# stopwatch.net
KiCad netlist of a schematic drawn in EAGLE
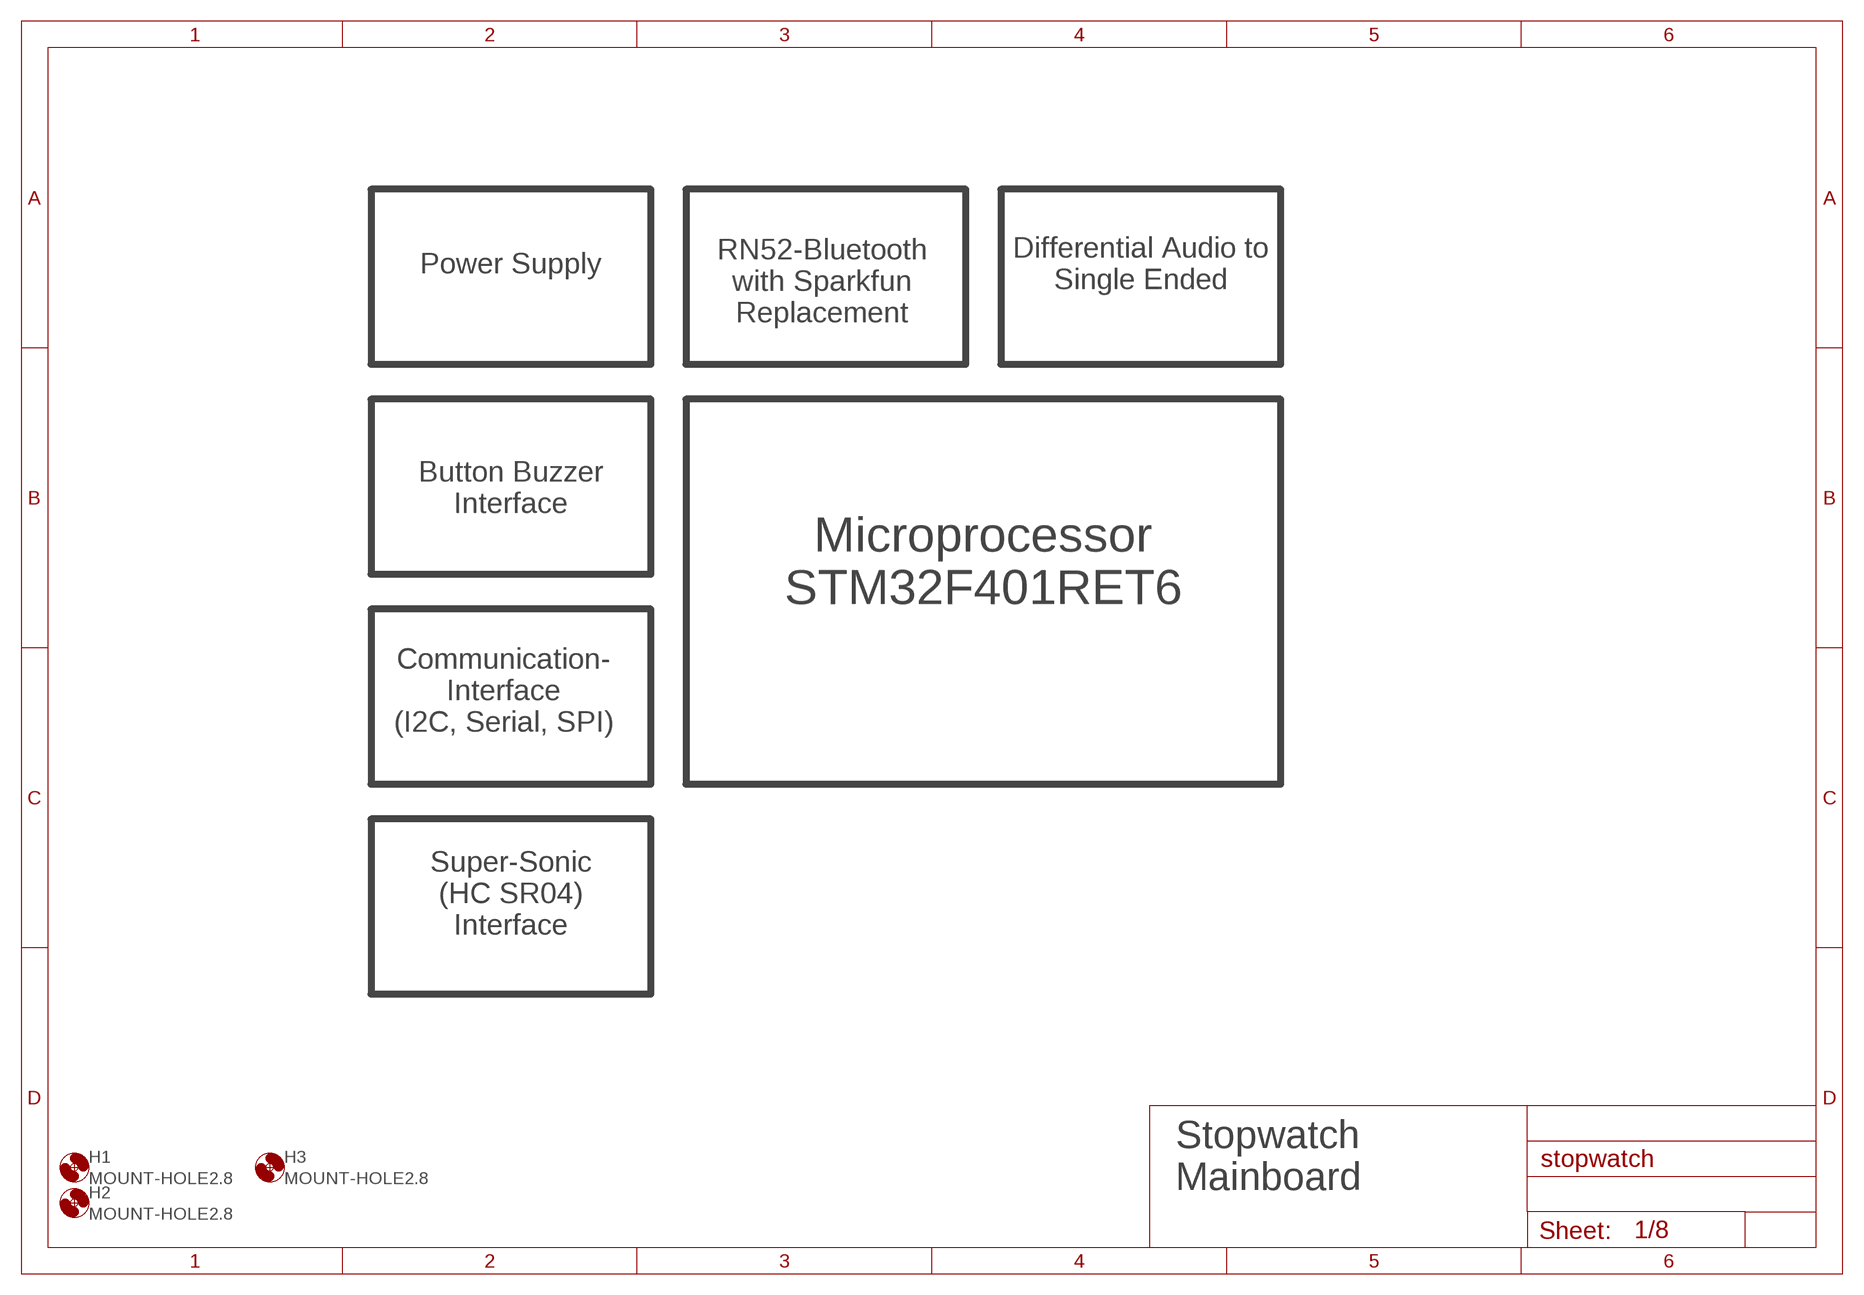
[diagram p0: schematic, sheet 1]
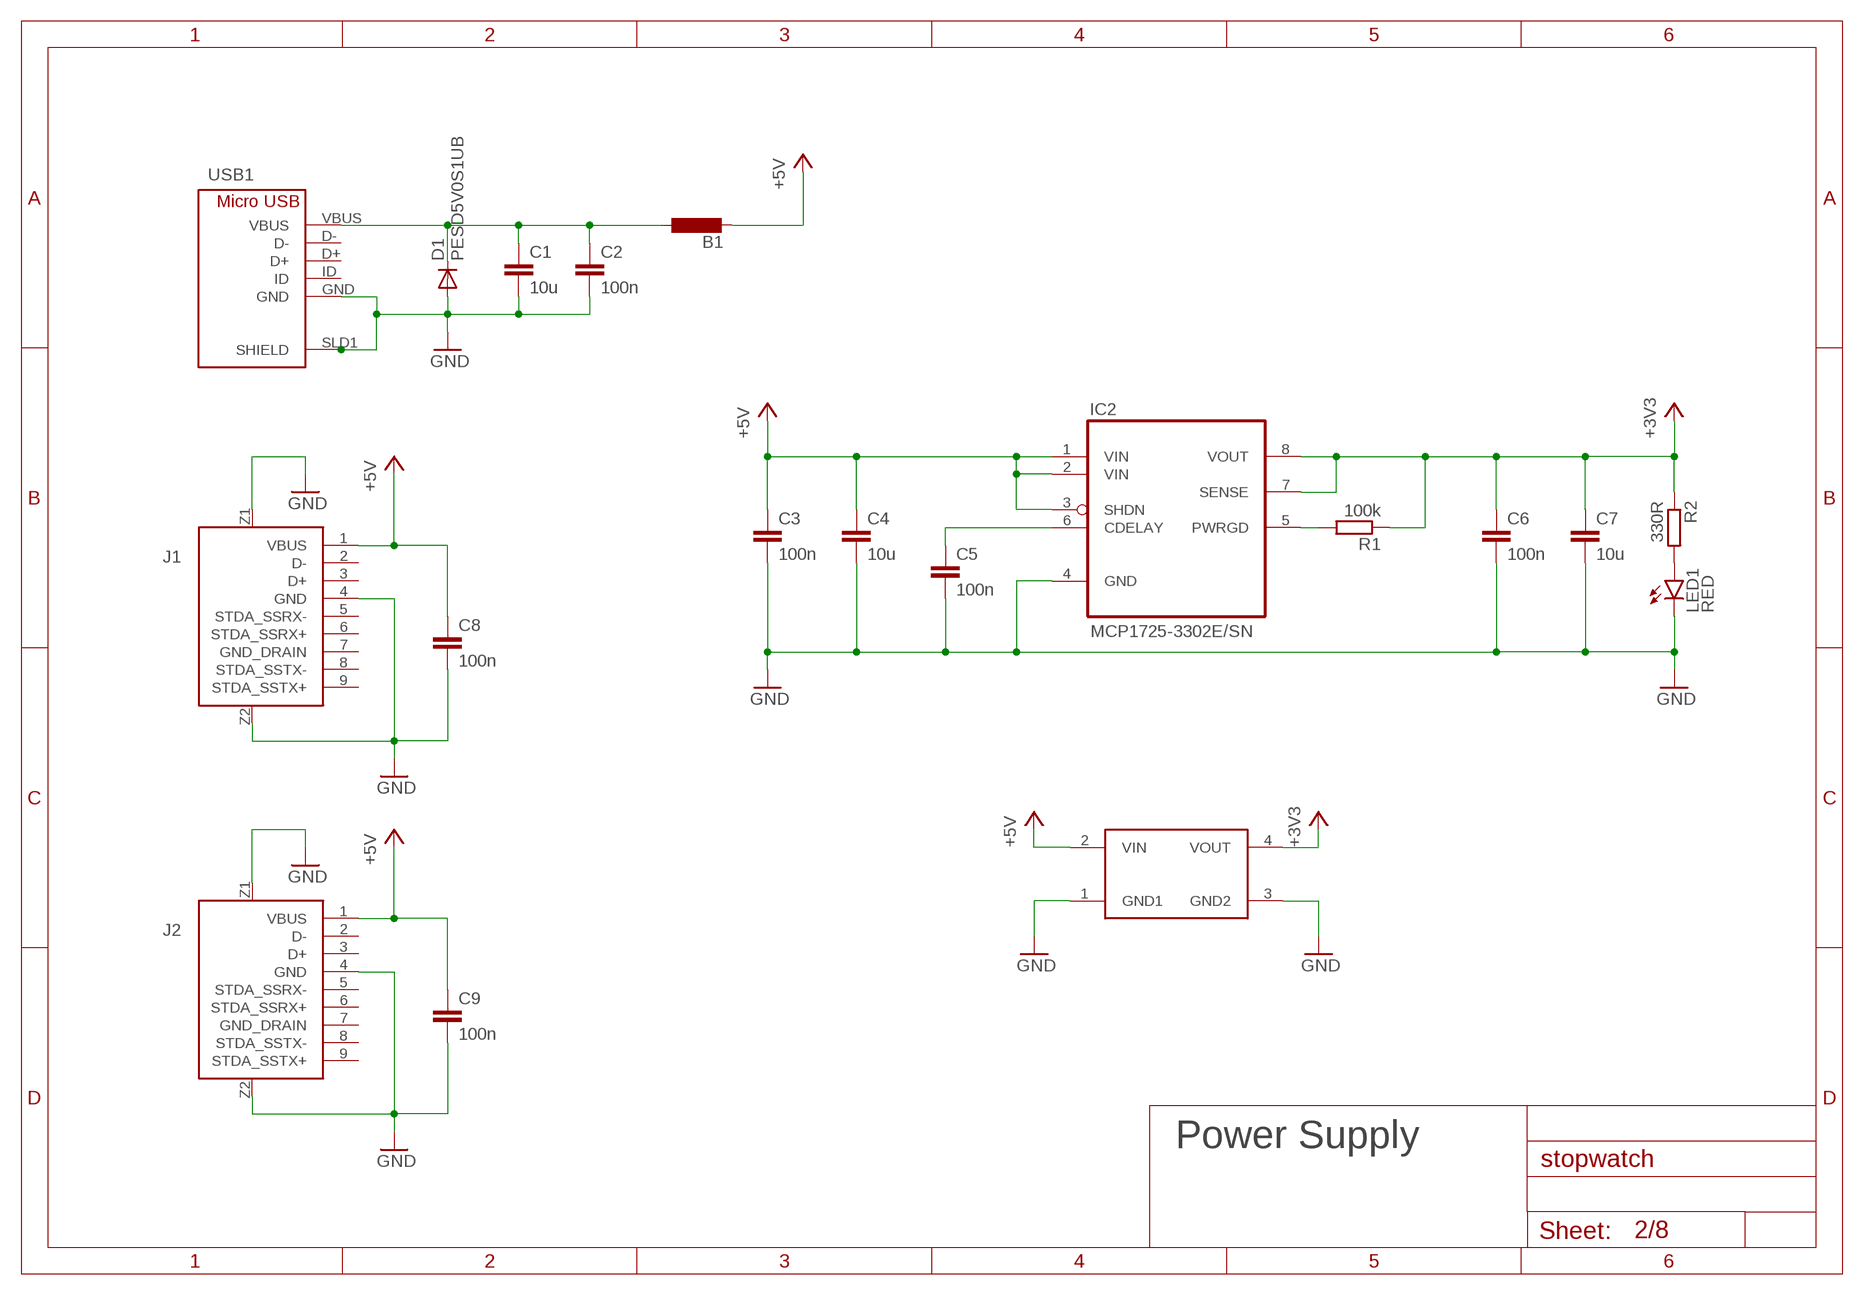
[diagram p1: schematic, sheet 2]
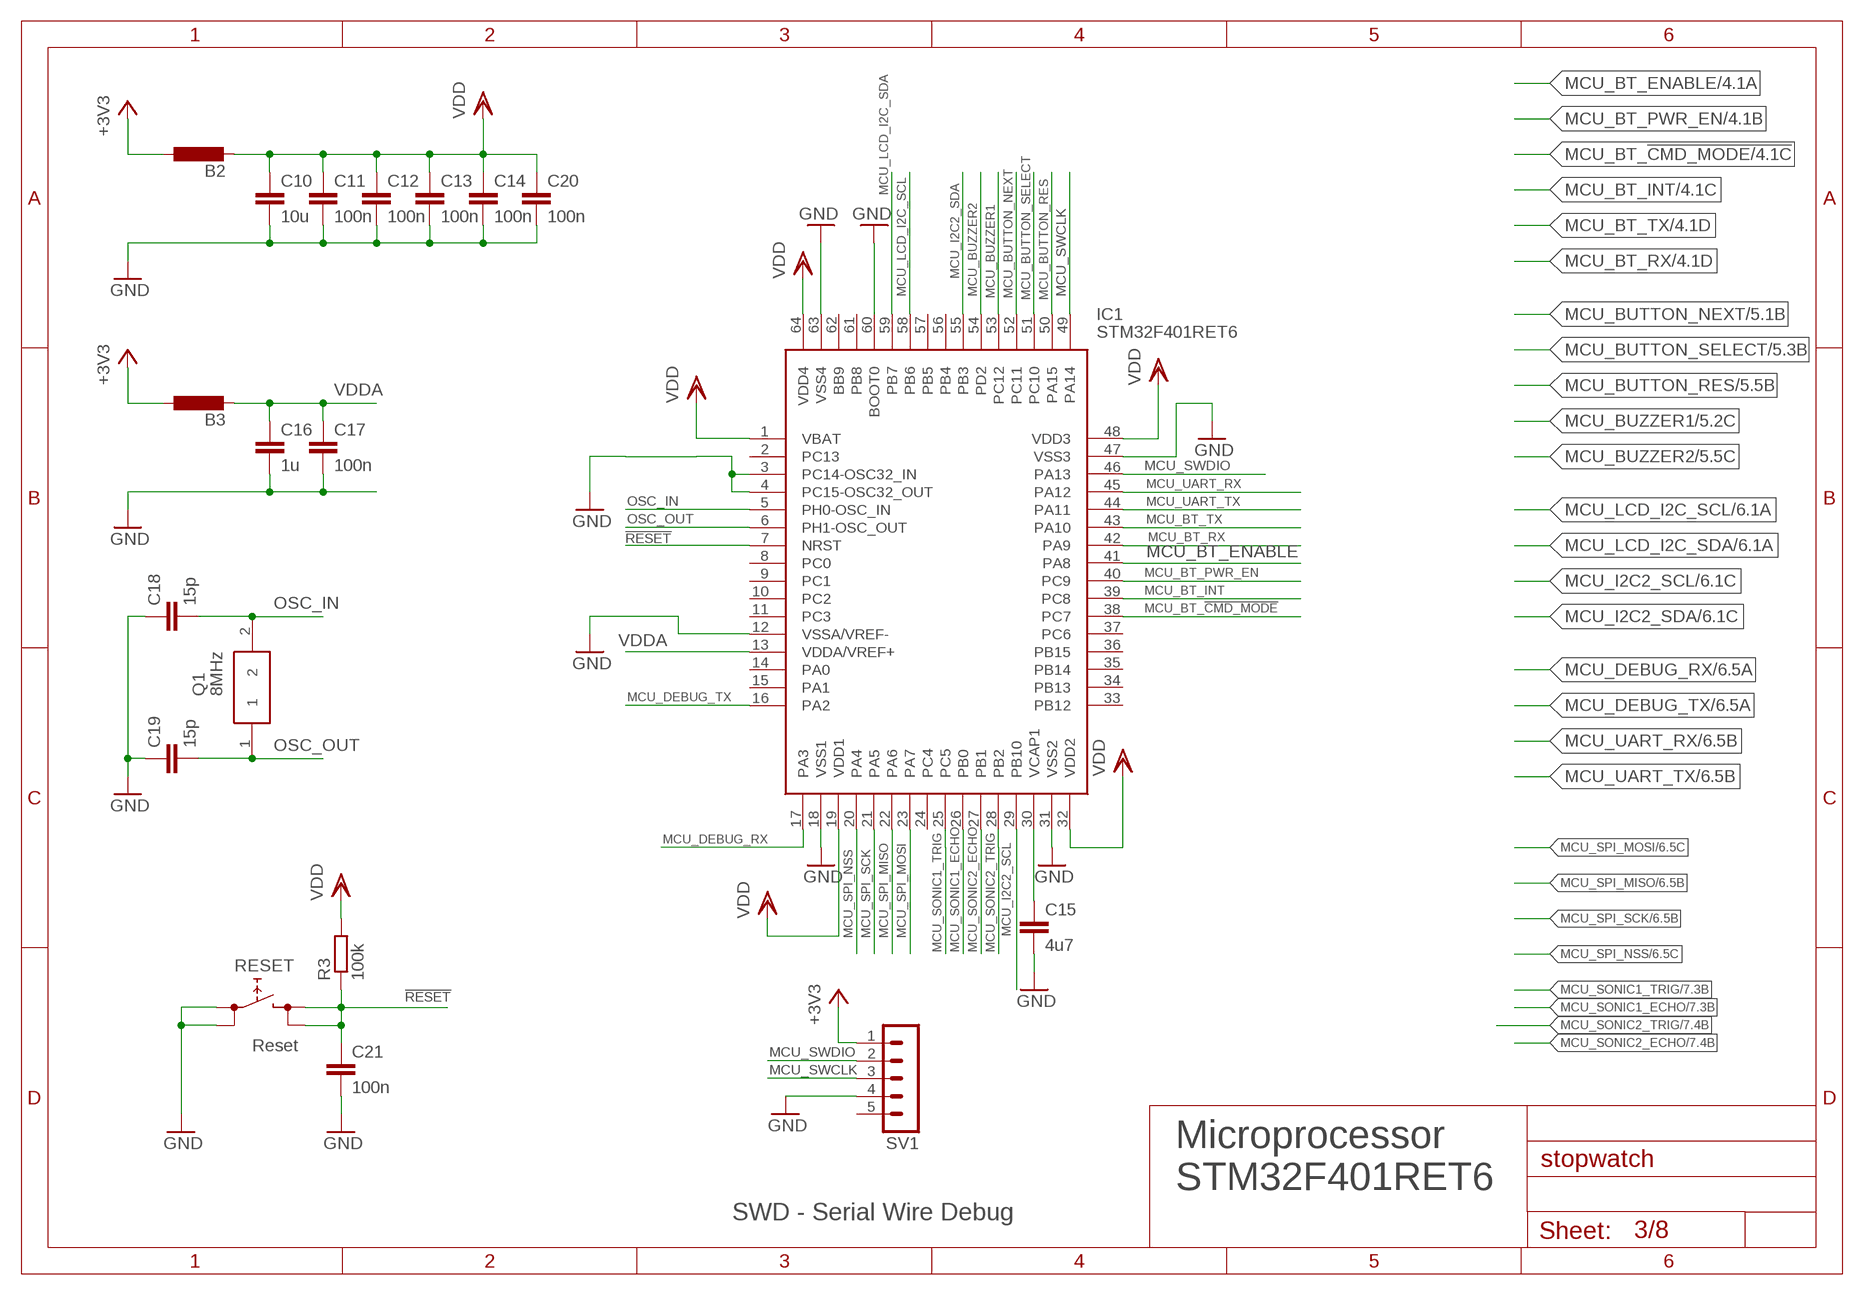
[diagram p2: schematic, sheet 3]
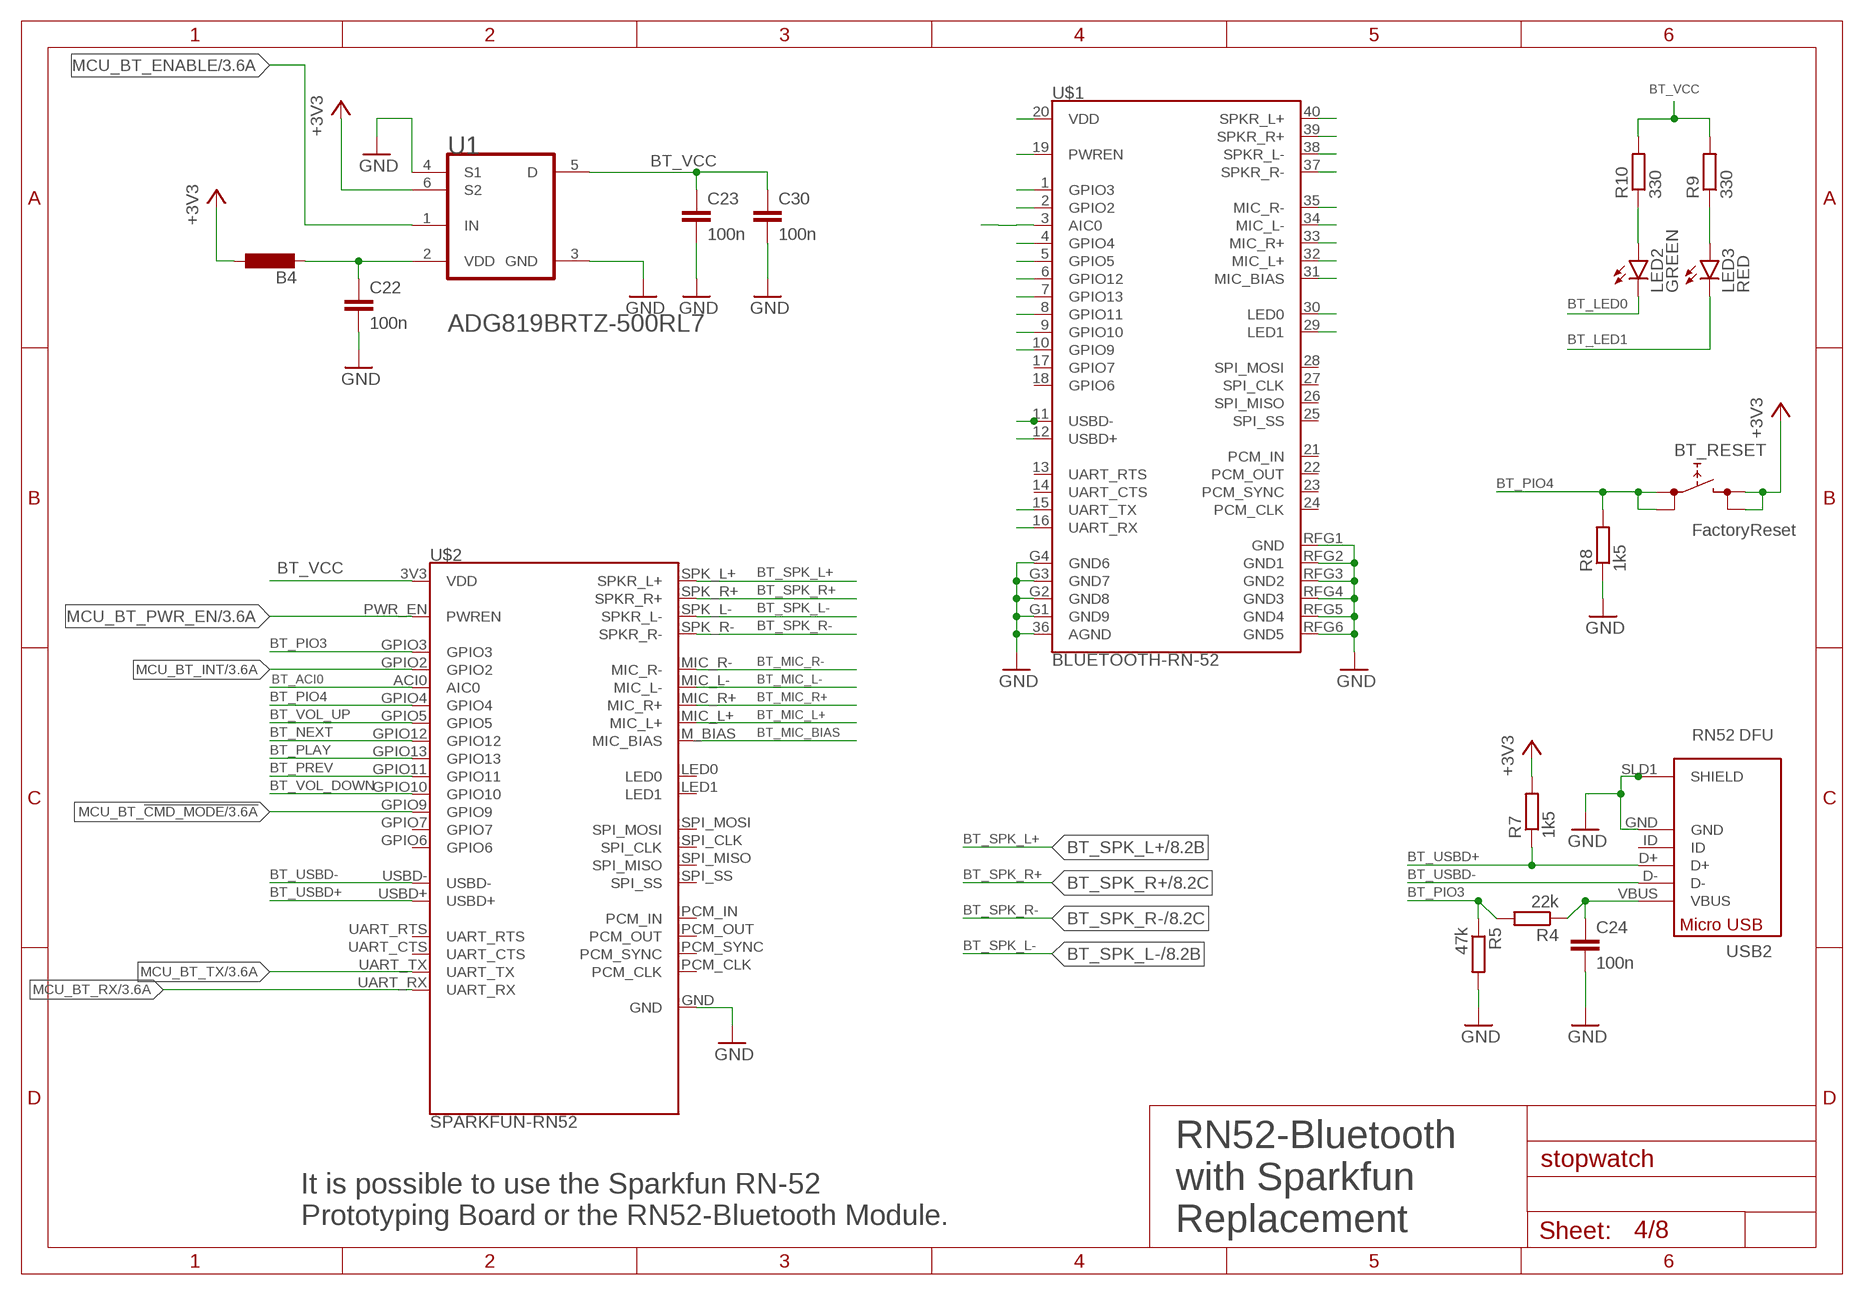
[diagram p3: schematic, sheet 4]
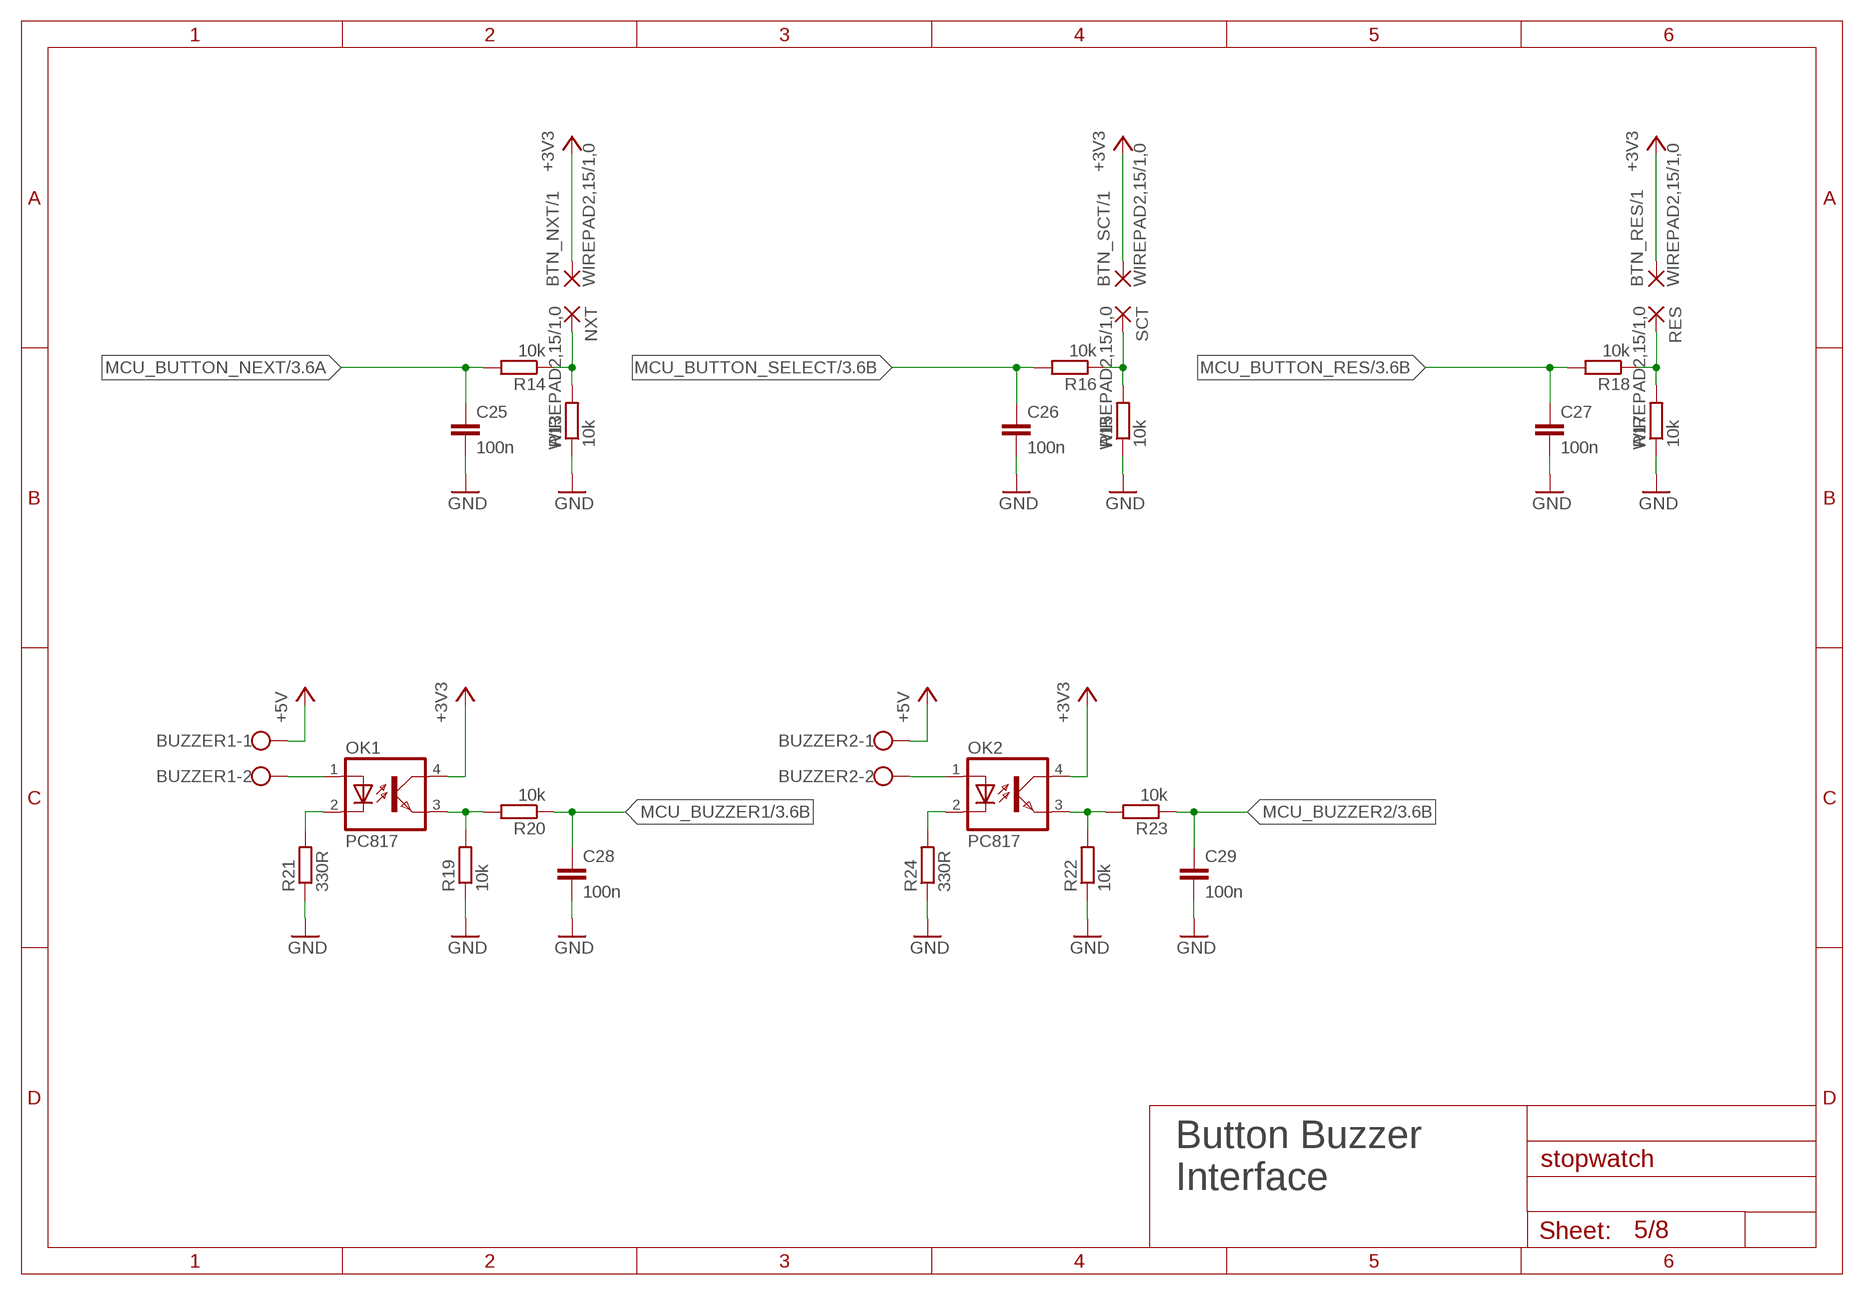
[diagram p4: schematic, sheet 5]
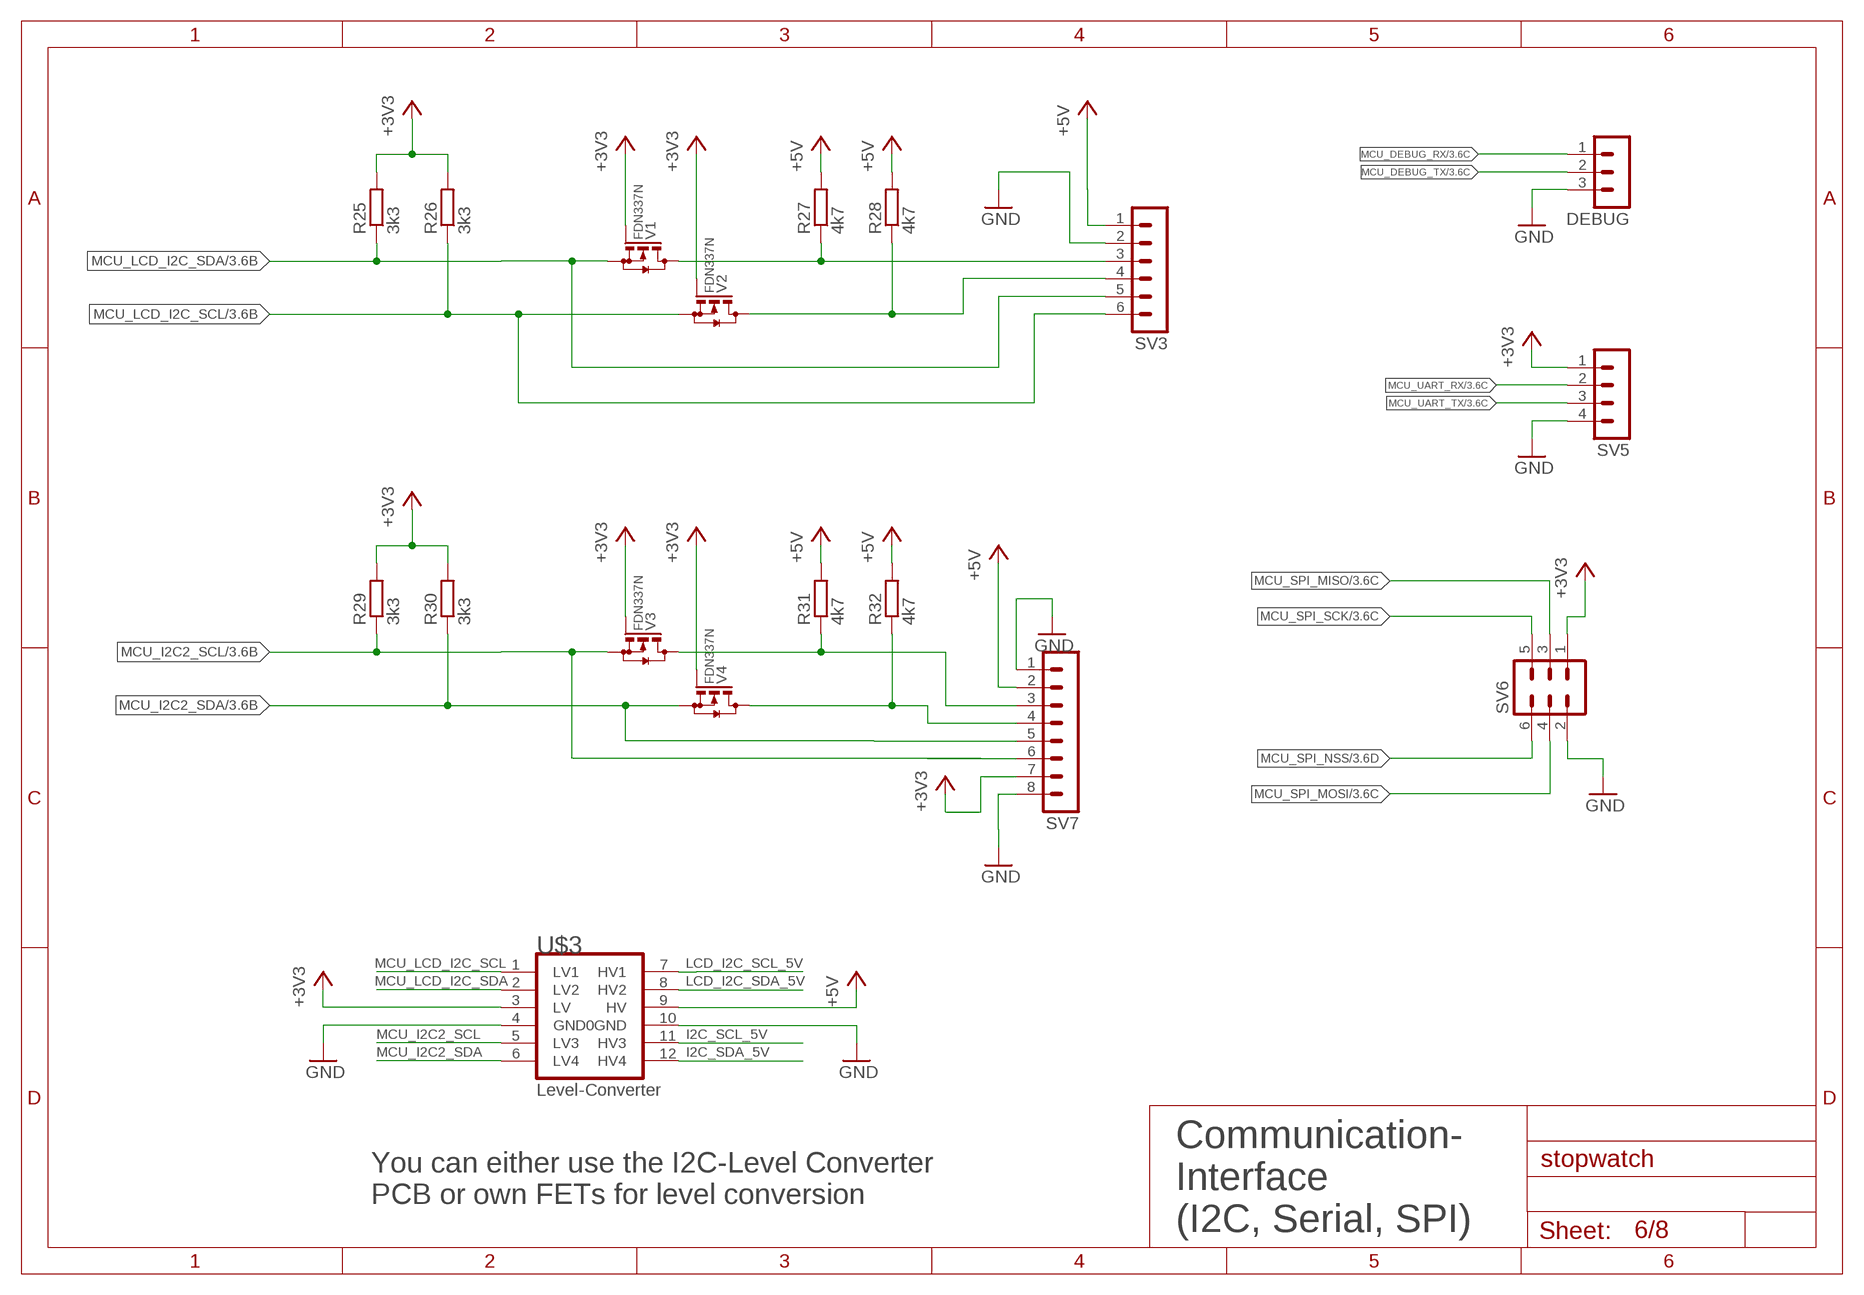
[diagram p5: schematic, sheet 6]
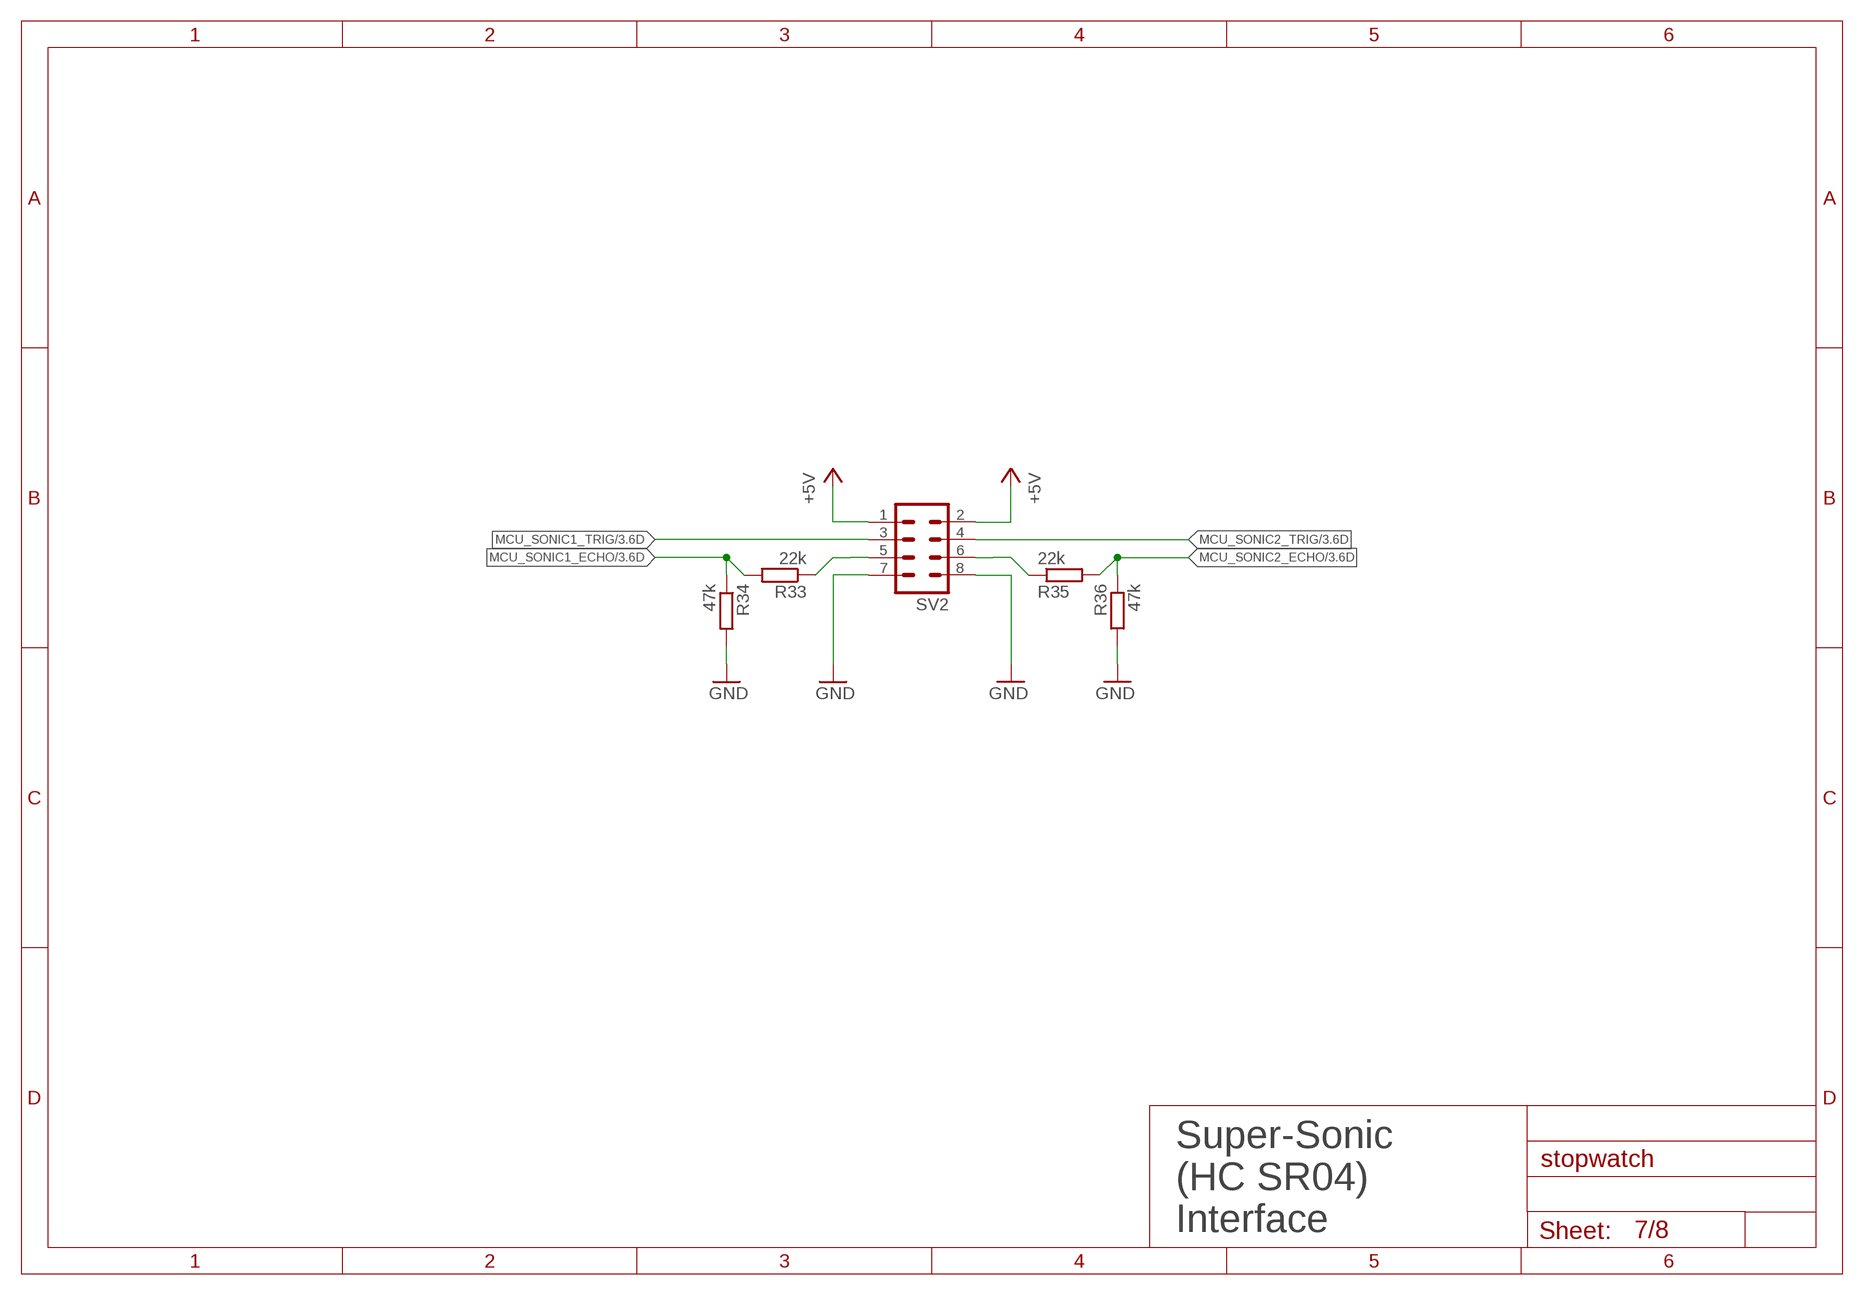
[diagram p6: schematic, sheet 7]
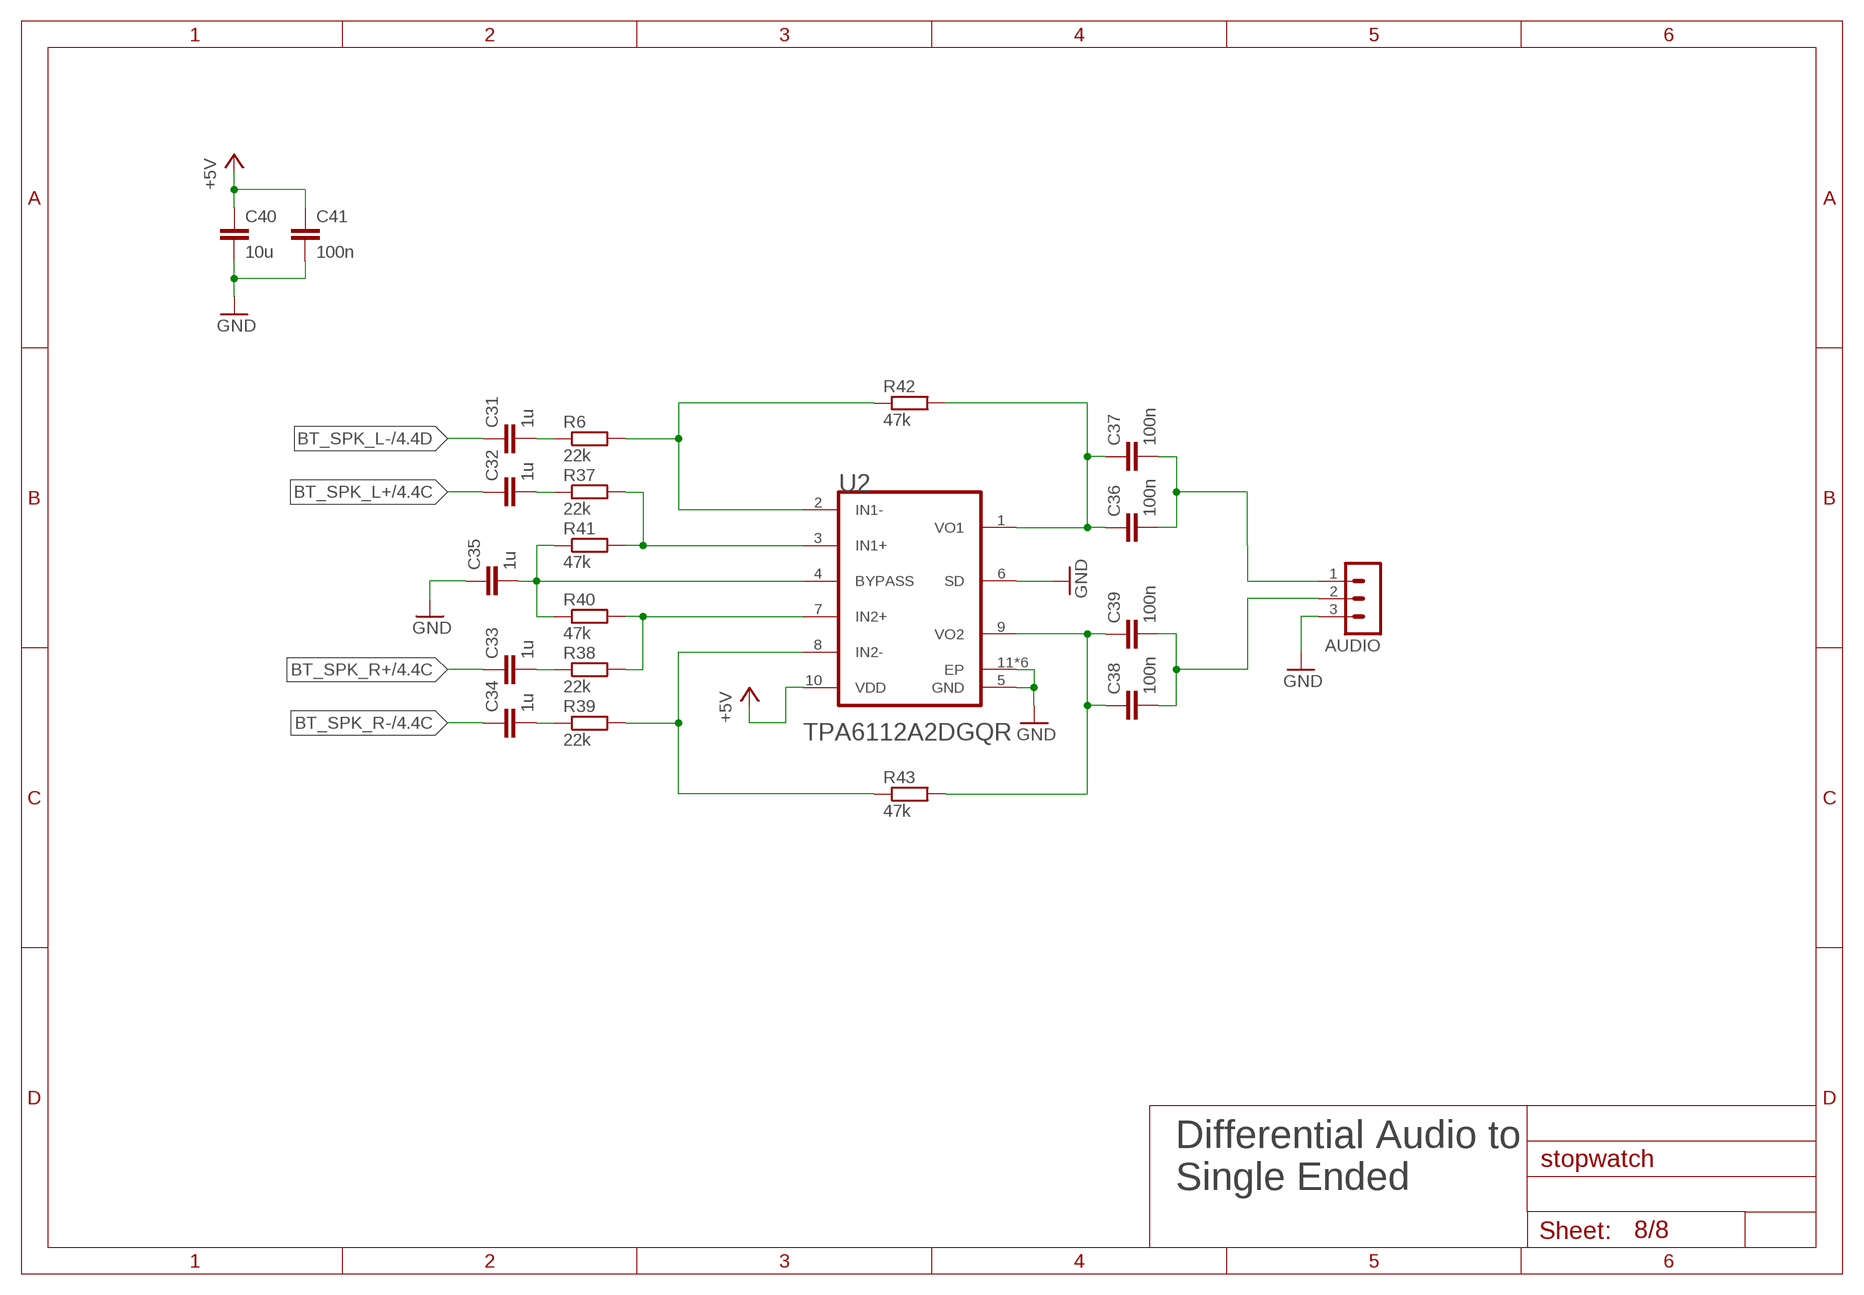
[diagram p7: schematic, sheet 8]

(export (version "E")
  (design (tool "Eeschema 10.0.6"))
  (components
    (comp (ref "BTN_NXT/1")
      (value "WIREPAD2,15/1,0")
      (footprint "eagle-import:2,15_1,0")
      (libsource (lib "eagle-import") (part "WIREPAD2,15/1,0"))
    )
    (comp (ref "BTN_RES/1")
      (value "WIREPAD2,15/1,0")
      (footprint "eagle-import:2,15_1,0")
      (libsource (lib "eagle-import") (part "WIREPAD2,15/1,0"))
    )
    (comp (ref "BTN_SCT/1")
      (value "WIREPAD2,15/1,0")
      (footprint "eagle-import:2,15_1,0")
      (libsource (lib "eagle-import") (part "WIREPAD2,15/1,0"))
    )
    (comp (ref "BUZZER1")
      (value "W237-102")
      (footprint "eagle-import:W237-102")
      (fields (field (name "MPN") "237-102"))
      (libsource (lib "eagle-import") (part "W237-102"))
    )
    (comp (ref "BUZZER2")
      (value "W237-102")
      (footprint "eagle-import:W237-102")
      (fields (field (name "MPN") "237-102"))
      (libsource (lib "eagle-import") (part "W237-102"))
    )
    (comp (ref "C25")
      (value "100n")
      (footprint "eagle-import:C1206")
      (libsource (lib "eagle-import") (part "C-EUC1206"))
    )
    (comp (ref "C26")
      (value "100n")
      (footprint "eagle-import:C1206")
      (libsource (lib "eagle-import") (part "C-EUC1206"))
    )
    (comp (ref "C27")
      (value "100n")
      (footprint "eagle-import:C1206")
      (libsource (lib "eagle-import") (part "C-EUC1206"))
    )
    (comp (ref "C28")
      (value "100n")
      (footprint "eagle-import:C1206")
      (libsource (lib "eagle-import") (part "C-EUC1206"))
    )
    (comp (ref "C29")
      (value "100n")
      (footprint "eagle-import:C1206")
      (libsource (lib "eagle-import") (part "C-EUC1206"))
    )
    (comp (ref "NXT")
      (value "WIREPAD2,15/1,0")
      (footprint "eagle-import:2,15_1,0")
      (libsource (lib "eagle-import") (part "WIREPAD2,15/1,0"))
    )
    (comp (ref "OK1")
      (value "PC817")
      (footprint "eagle-import:DIL04")
      (fields (field (name "MPN") "PC817X4J000F"))
      (libsource (lib "eagle-import") (part "PC817"))
    )
    (comp (ref "OK2")
      (value "PC817")
      (footprint "eagle-import:DIL04")
      (fields (field (name "MPN") "PC817X4J000F"))
      (libsource (lib "eagle-import") (part "PC817"))
    )
    (comp (ref "R13")
      (value "10k")
      (footprint "eagle-import:R1206")
      (libsource (lib "eagle-import") (part "R-EU_R1206"))
    )
    (comp (ref "R14")
      (value "10k")
      (footprint "eagle-import:R1206")
      (libsource (lib "eagle-import") (part "R-EU_R1206"))
    )
    (comp (ref "R15")
      (value "10k")
      (footprint "eagle-import:R1206")
      (libsource (lib "eagle-import") (part "R-EU_R1206"))
    )
    (comp (ref "R16")
      (value "10k")
      (footprint "eagle-import:R1206")
      (libsource (lib "eagle-import") (part "R-EU_R1206"))
    )
    (comp (ref "R17")
      (value "10k")
      (footprint "eagle-import:R1206")
      (libsource (lib "eagle-import") (part "R-EU_R1206"))
    )
    (comp (ref "R18")
      (value "10k")
      (footprint "eagle-import:R1206")
      (libsource (lib "eagle-import") (part "R-EU_R1206"))
    )
    (comp (ref "R19")
      (value "10k")
      (footprint "eagle-import:R1206")
      (libsource (lib "eagle-import") (part "R-EU_R1206"))
    )
    (comp (ref "R20")
      (value "10k")
      (footprint "eagle-import:R1206")
      (libsource (lib "eagle-import") (part "R-EU_R1206"))
    )
    (comp (ref "R21")
      (value "330R")
      (footprint "eagle-import:R1206")
      (libsource (lib "eagle-import") (part "R-EU_R1206"))
    )
    (comp (ref "R22")
      (value "10k")
      (footprint "eagle-import:R1206")
      (libsource (lib "eagle-import") (part "R-EU_R1206"))
    )
    (comp (ref "R23")
      (value "10k")
      (footprint "eagle-import:R1206")
      (libsource (lib "eagle-import") (part "R-EU_R1206"))
    )
    (comp (ref "R24")
      (value "330R")
      (footprint "eagle-import:R1206")
      (libsource (lib "eagle-import") (part "R-EU_R1206"))
    )
    (comp (ref "RES")
      (value "WIREPAD2,15/1,0")
      (footprint "eagle-import:2,15_1,0")
      (libsource (lib "eagle-import") (part "WIREPAD2,15/1,0"))
    )
    (comp (ref "SCT")
      (value "WIREPAD2,15/1,0")
      (footprint "eagle-import:2,15_1,0")
      (libsource (lib "eagle-import") (part "WIREPAD2,15/1,0"))
    )
    (comp (ref "B2")
      (value "B-EU_B0805")
      (footprint "eagle-import:L0805")
      (libsource (lib "eagle-import") (part "B-EU_B0805"))
    )
    (comp (ref "B3")
      (value "B-EU_B0805")
      (footprint "eagle-import:L0805")
      (libsource (lib "eagle-import") (part "B-EU_B0805"))
    )
    (comp (ref "C10")
      (value "10u")
      (footprint "eagle-import:C1206")
      (libsource (lib "eagle-import") (part "C-EUC1206"))
    )
    (comp (ref "C11")
      (value "100n")
      (footprint "eagle-import:C1206")
      (libsource (lib "eagle-import") (part "C-EUC1206"))
    )
    (comp (ref "C12")
      (value "100n")
      (footprint "eagle-import:C1206")
      (libsource (lib "eagle-import") (part "C-EUC1206"))
    )
    (comp (ref "C13")
      (value "100n")
      (footprint "eagle-import:C1206")
      (libsource (lib "eagle-import") (part "C-EUC1206"))
    )
    (comp (ref "C14")
      (value "100n")
      (footprint "eagle-import:C1206")
      (libsource (lib "eagle-import") (part "C-EUC1206"))
    )
    (comp (ref "C15")
      (value "4u7")
      (footprint "eagle-import:C1206")
      (libsource (lib "eagle-import") (part "C-EUC1206"))
    )
    (comp (ref "C16")
      (value "1u")
      (footprint "eagle-import:C1206")
      (libsource (lib "eagle-import") (part "C-EUC1206"))
    )
    (comp (ref "C17")
      (value "100n")
      (footprint "eagle-import:C1206")
      (libsource (lib "eagle-import") (part "C-EUC1206"))
    )
    (comp (ref "C18")
      (value "15p")
      (footprint "eagle-import:C1206")
      (libsource (lib "eagle-import") (part "C-EUC1206"))
    )
    (comp (ref "C19")
      (value "15p")
      (footprint "eagle-import:C1206")
      (libsource (lib "eagle-import") (part "C-EUC1206"))
    )
    (comp (ref "C20")
      (value "100n")
      (footprint "eagle-import:C1206")
      (libsource (lib "eagle-import") (part "C-EUC1206"))
    )
    (comp (ref "C21")
      (value "100n")
      (footprint "eagle-import:C1206")
      (libsource (lib "eagle-import") (part "C-EUC1206"))
    )
    (comp (ref "IC1")
      (value "STM32F401RET6")
      (footprint "eagle-import:QFP50P1200X1200X160-64N")
      (fields (field (name "RS_PART_NUMBER") "1661154"))
      (libsource (lib "eagle-import") (part "STM32F401RET6"))
    )
    (comp (ref "Q1")
      (value "8MHz")
      (footprint "eagle-import:FOXSDLF_080-20")
      (fields
        (field (name "MANUFACTURER_PART_NUMBER") "FOXSDLF/080-20")
        (field (name "RS_PART_NUMBER") "1734329")
      )
      (libsource (lib "eagle-import") (part "FOXSDLF_080-20"))
    )
    (comp (ref "R3")
      (value "100k")
      (footprint "eagle-import:R1206")
      (libsource (lib "eagle-import") (part "R-EU_R1206"))
    )
    (comp (ref "RESET")
      (value "Reset")
      (footprint "eagle-import:TASTER_SMD_LSG-LSH1301XX")
      (libsource (lib "eagle-import") (part "TASTER_SMD"))
    )
    (comp (ref "SV1")
      (value "MA05-1")
      (footprint "eagle-import:MA05-1")
      (libsource (lib "eagle-import") (part "MA05-1"))
    )
    (comp (ref "B1")
      (value "B-EU_B0805")
      (footprint "eagle-import:L0805")
      (libsource (lib "eagle-import") (part "B-EU_B0805"))
    )
    (comp (ref "C1")
      (value "10u")
      (footprint "eagle-import:C1206")
      (libsource (lib "eagle-import") (part "C-EUC1206"))
    )
    (comp (ref "C2")
      (value "100n")
      (footprint "eagle-import:C1206")
      (libsource (lib "eagle-import") (part "C-EUC1206"))
    )
    (comp (ref "C3")
      (value "100n")
      (footprint "eagle-import:C1206")
      (libsource (lib "eagle-import") (part "C-EUC1206"))
    )
    (comp (ref "C4")
      (value "10u")
      (footprint "eagle-import:C1206")
      (libsource (lib "eagle-import") (part "C-EUC1206"))
    )
    (comp (ref "C5")
      (value "100n")
      (footprint "eagle-import:C1206")
      (libsource (lib "eagle-import") (part "C-EUC1206"))
    )
    (comp (ref "C6")
      (value "100n")
      (footprint "eagle-import:C1206")
      (libsource (lib "eagle-import") (part "C-EUC1206"))
    )
    (comp (ref "C7")
      (value "10u")
      (footprint "eagle-import:C1206")
      (libsource (lib "eagle-import") (part "C-EUC1206"))
    )
    (comp (ref "C8")
      (value "100n")
      (footprint "eagle-import:C1206")
      (libsource (lib "eagle-import") (part "C-EUC1206"))
    )
    (comp (ref "C9")
      (value "100n")
      (footprint "eagle-import:C1206")
      (libsource (lib "eagle-import") (part "C-EUC1206"))
    )
    (comp (ref "D1")
      (value "PESD5V0S1UB")
      (footprint "eagle-import:SOD523")
      (libsource (lib "eagle-import") (part "DIODE-SOD523"))
    )
    (comp (ref "IC2")
      (value "MCP1725-3302E/SN")
      (footprint "eagle-import:SOIC127P600X175-8N")
      (libsource (lib "eagle-import") (part "MCP1725-3302E/SN"))
    )
    (comp (ref "J1")
      (value "USB-A3-0")
      (footprint "eagle-import:USB3_TYPE_A")
      (libsource (lib "eagle-import") (part "USB-A3-0"))
    )
    (comp (ref "J2")
      (value "USB-A3-0")
      (footprint "eagle-import:USB3_TYPE_A")
      (libsource (lib "eagle-import") (part "USB-A3-0"))
    )
    (comp (ref "LED1")
      (value "RED")
      (footprint "eagle-import:CHIPLED_1206")
      (libsource (lib "eagle-import") (part "LEDCHIPLED_1206"))
    )
    (comp (ref "R1")
      (value "100k")
      (footprint "eagle-import:R1206")
      (libsource (lib "eagle-import") (part "R-EU_R1206"))
    )
    (comp (ref "R2")
      (value "330R")
      (footprint "eagle-import:R1206")
      (libsource (lib "eagle-import") (part "R-EU_R1206"))
    )
    (comp (ref "U$4")
      (value "RC-STEP-DOWN")
      (footprint "eagle-import:RC-STEP-DOWN")
      (libsource (lib "eagle-import") (part "RC-STEP-DOWN"))
    )
    (comp (ref "USB1")
      (value "MICRO-USB")
      (footprint "eagle-import:ZX62B5PA")
      (libsource (lib "eagle-import") (part "MICRO-USB"))
    )
    (comp (ref "DEBUG")
      (value "MA03-1")
      (footprint "eagle-import:MA03-1")
      (libsource (lib "eagle-import") (part "MA03-1"))
    )
    (comp (ref "R25")
      (value "3k3")
      (footprint "eagle-import:R1206")
      (libsource (lib "eagle-import") (part "R-EU_R1206"))
    )
    (comp (ref "R26")
      (value "3k3")
      (footprint "eagle-import:R1206")
      (libsource (lib "eagle-import") (part "R-EU_R1206"))
    )
    (comp (ref "R27")
      (value "4k7")
      (footprint "eagle-import:R1206")
      (libsource (lib "eagle-import") (part "R-EU_R1206"))
    )
    (comp (ref "R28")
      (value "4k7")
      (footprint "eagle-import:R1206")
      (libsource (lib "eagle-import") (part "R-EU_R1206"))
    )
    (comp (ref "R29")
      (value "3k3")
      (footprint "eagle-import:R1206")
      (libsource (lib "eagle-import") (part "R-EU_R1206"))
    )
    (comp (ref "R30")
      (value "3k3")
      (footprint "eagle-import:R1206")
      (libsource (lib "eagle-import") (part "R-EU_R1206"))
    )
    (comp (ref "R31")
      (value "4k7")
      (footprint "eagle-import:R1206")
      (libsource (lib "eagle-import") (part "R-EU_R1206"))
    )
    (comp (ref "R32")
      (value "4k7")
      (footprint "eagle-import:R1206")
      (libsource (lib "eagle-import") (part "R-EU_R1206"))
    )
    (comp (ref "SV3")
      (value "MA06-1")
      (footprint "eagle-import:MA06-1")
      (libsource (lib "eagle-import") (part "MA06-1"))
    )
    (comp (ref "SV5")
      (value "MA04-1")
      (footprint "eagle-import:MA04-1")
      (libsource (lib "eagle-import") (part "MA04-1"))
    )
    (comp (ref "SV6")
      (value "MA03-2")
      (footprint "eagle-import:MA03-2")
      (libsource (lib "eagle-import") (part "MA03-2"))
    )
    (comp (ref "SV7")
      (value "MA08-1")
      (footprint "eagle-import:MA08-1")
      (libsource (lib "eagle-import") (part "MA08-1"))
    )
    (comp (ref "U$3")
      (value "I2C-LEVELCONVERTER-PCB")
      (footprint "eagle-import:I2C-LEVELCONVERTER-PCB")
      (libsource (lib "eagle-import") (part "I2C-LEVELCONVERTER-PCB"))
    )
    (comp (ref "V1")
      (value "FDN337N")
      (footprint "eagle-import:SOT23")
      (fields (field (name "MF") "FAIRCHILD SEMICONDUCTOR"))
      (libsource (lib "eagle-import") (part "FDN337N"))
    )
    (comp (ref "V2")
      (value "FDN337N")
      (footprint "eagle-import:SOT23")
      (fields (field (name "MF") "FAIRCHILD SEMICONDUCTOR"))
      (libsource (lib "eagle-import") (part "FDN337N"))
    )
    (comp (ref "V3")
      (value "FDN337N")
      (footprint "eagle-import:SOT23")
      (fields (field (name "MF") "FAIRCHILD SEMICONDUCTOR"))
      (libsource (lib "eagle-import") (part "FDN337N"))
    )
    (comp (ref "V4")
      (value "FDN337N")
      (footprint "eagle-import:SOT23")
      (fields (field (name "MF") "FAIRCHILD SEMICONDUCTOR"))
      (libsource (lib "eagle-import") (part "FDN337N"))
    )
    (comp (ref "R33")
      (value "22k")
      (footprint "eagle-import:R1206")
      (libsource (lib "eagle-import") (part "R-EU_R1206"))
    )
    (comp (ref "R34")
      (value "47k")
      (footprint "eagle-import:R1206")
      (libsource (lib "eagle-import") (part "R-EU_R1206"))
    )
    (comp (ref "R35")
      (value "22k")
      (footprint "eagle-import:R1206")
      (libsource (lib "eagle-import") (part "R-EU_R1206"))
    )
    (comp (ref "R36")
      (value "47k")
      (footprint "eagle-import:R1206")
      (libsource (lib "eagle-import") (part "R-EU_R1206"))
    )
    (comp (ref "SV2")
      (value "MA04-2")
      (footprint "eagle-import:MA04-2")
      (libsource (lib "eagle-import") (part "MA04-2"))
    )
    (comp (ref "AUDIO")
      (value "MA03-1")
      (footprint "eagle-import:MA03-1")
      (libsource (lib "eagle-import") (part "MA03-1"))
    )
    (comp (ref "C31")
      (value "1u")
      (footprint "eagle-import:C1206")
      (libsource (lib "eagle-import") (part "C-EUC1206"))
    )
    (comp (ref "C32")
      (value "1u")
      (footprint "eagle-import:C1206")
      (libsource (lib "eagle-import") (part "C-EUC1206"))
    )
    (comp (ref "C33")
      (value "1u")
      (footprint "eagle-import:C1206")
      (libsource (lib "eagle-import") (part "C-EUC1206"))
    )
    (comp (ref "C34")
      (value "1u")
      (footprint "eagle-import:C1206")
      (libsource (lib "eagle-import") (part "C-EUC1206"))
    )
    (comp (ref "C35")
      (value "1u")
      (footprint "eagle-import:C1206")
      (libsource (lib "eagle-import") (part "C-EUC1206"))
    )
    (comp (ref "C36")
      (value "100n")
      (footprint "eagle-import:C1206")
      (libsource (lib "eagle-import") (part "C-EUC1206"))
    )
    (comp (ref "C37")
      (value "100n")
      (footprint "eagle-import:C1206")
      (libsource (lib "eagle-import") (part "C-EUC1206"))
    )
    (comp (ref "C38")
      (value "100n")
      (footprint "eagle-import:C1206")
      (libsource (lib "eagle-import") (part "C-EUC1206"))
    )
    (comp (ref "C39")
      (value "100n")
      (footprint "eagle-import:C1206")
      (libsource (lib "eagle-import") (part "C-EUC1206"))
    )
    (comp (ref "C40")
      (value "10u")
      (footprint "eagle-import:C1206")
      (libsource (lib "eagle-import") (part "C-EUC1206"))
    )
    (comp (ref "C41")
      (value "100n")
      (footprint "eagle-import:C1206")
      (libsource (lib "eagle-import") (part "C-EUC1206"))
    )
    (comp (ref "R6")
      (value "22k")
      (footprint "eagle-import:R1206")
      (libsource (lib "eagle-import") (part "R-EU_R1206"))
    )
    (comp (ref "R37")
      (value "22k")
      (footprint "eagle-import:R1206")
      (libsource (lib "eagle-import") (part "R-EU_R1206"))
    )
    (comp (ref "R38")
      (value "22k")
      (footprint "eagle-import:R1206")
      (libsource (lib "eagle-import") (part "R-EU_R1206"))
    )
    (comp (ref "R39")
      (value "22k")
      (footprint "eagle-import:R1206")
      (libsource (lib "eagle-import") (part "R-EU_R1206"))
    )
    (comp (ref "R40")
      (value "47k")
      (footprint "eagle-import:R1206")
      (libsource (lib "eagle-import") (part "R-EU_R1206"))
    )
    (comp (ref "R41")
      (value "47k")
      (footprint "eagle-import:R1206")
      (libsource (lib "eagle-import") (part "R-EU_R1206"))
    )
    (comp (ref "R42")
      (value "47k")
      (footprint "eagle-import:R1206")
      (libsource (lib "eagle-import") (part "R-EU_R1206"))
    )
    (comp (ref "R43")
      (value "47k")
      (footprint "eagle-import:R1206")
      (libsource (lib "eagle-import") (part "R-EU_R1206"))
    )
    (comp (ref "U2")
      (value "TEXAS_INSTRUMENTS_TPA6112A2DGQRTEXAS_INSTRUMENTS_TPA6112A2DGQR_0_1")
      (footprint "eagle-import:TEXAS_INSTRUMENTS_TPA6112A2DGQR_1")
      (fields (field (name "MF") "Texas Instruments") (field (name "MPN") "TPA6112A2DGQR"))
      (libsource (lib "eagle-import") (part "TEXAS_INSTRUMENTS_TPA6112A2DGQRTEXAS_INSTRUMENTS_TPA6112A2DGQR_0_1"))
    )
    (comp (ref "B4")
      (value "B-EU_B0805")
      (footprint "eagle-import:L0805")
      (libsource (lib "eagle-import") (part "B-EU_B0805"))
    )
    (comp (ref "BT_RESET")
      (value "FactoryReset")
      (footprint "eagle-import:TASTER_SMD_LSG-LSH1301XX")
      (libsource (lib "eagle-import") (part "TASTER_SMD"))
    )
    (comp (ref "C22")
      (value "100n")
      (footprint "eagle-import:C1206")
      (libsource (lib "eagle-import") (part "C-EUC1206"))
    )
    (comp (ref "C23")
      (value "100n")
      (footprint "eagle-import:C1206")
      (libsource (lib "eagle-import") (part "C-EUC1206"))
    )
    (comp (ref "C24")
      (value "100n")
      (footprint "eagle-import:C1206")
      (libsource (lib "eagle-import") (part "C-EUC1206"))
    )
    (comp (ref "C30")
      (value "100n")
      (footprint "eagle-import:C1206")
      (libsource (lib "eagle-import") (part "C-EUC1206"))
    )
    (comp (ref "LED2")
      (value "GREEN")
      (footprint "eagle-import:CHIPLED_1206")
      (libsource (lib "eagle-import") (part "LEDCHIPLED_1206"))
    )
    (comp (ref "LED3")
      (value "RED")
      (footprint "eagle-import:CHIPLED_1206")
      (libsource (lib "eagle-import") (part "LEDCHIPLED_1206"))
    )
    (comp (ref "R4")
      (value "22k")
      (footprint "eagle-import:R1206")
      (libsource (lib "eagle-import") (part "R-EU_R1206"))
    )
    (comp (ref "R5")
      (value "47k")
      (footprint "eagle-import:R1206")
      (libsource (lib "eagle-import") (part "R-EU_R1206"))
    )
    (comp (ref "R7")
      (value "1k5")
      (footprint "eagle-import:R1206")
      (libsource (lib "eagle-import") (part "R-EU_R1206"))
    )
    (comp (ref "R8")
      (value "1k5")
      (footprint "eagle-import:R1206")
      (libsource (lib "eagle-import") (part "R-EU_R1206"))
    )
    (comp (ref "R9")
      (value "330")
      (footprint "eagle-import:R1206")
      (libsource (lib "eagle-import") (part "R-EU_R1206"))
    )
    (comp (ref "R10")
      (value "330")
      (footprint "eagle-import:R1206")
      (libsource (lib "eagle-import") (part "R-EU_R1206"))
    )
    (comp (ref "U$1")
      (value "BLUETOOTH-RN-52")
      (footprint "eagle-import:RN-52")
      (libsource (lib "eagle-import") (part "BLUETOOTH-RN-52"))
    )
    (comp (ref "U$2")
      (value "SPARKFUN-RN52")
      (footprint "eagle-import:SPARKFUN-RN52")
      (libsource (lib "eagle-import") (part "SPARKFUN-RN52"))
    )
    (comp (ref "U1")
      (value "ANALOG_DEVICES_ADG819BRTZ-500RL7ANALOG_DEVICES_ADG819BRTZ-500RL7_0_1")
      (footprint "eagle-import:ANALOG_DEVICES_ADG819BRTZ-500RL7_1")
      (fields (field (name "MF") "Analog Devices") (field (name "MPN") "ADG819BRTZ-500RL7"))
      (libsource (lib "eagle-import") (part "ANALOG_DEVICES_ADG819BRTZ-500RL7ANALOG_DEVICES_ADG819BRTZ-500RL7_0_1"))
    )
    (comp (ref "USB2")
      (value "MICRO-USB")
      (footprint "eagle-import:ZX62B5PA")
      (libsource (lib "eagle-import") (part "MICRO-USB"))
    )
    (comp (ref "H1")
      (value "MOUNT-HOLE2.8")
      (footprint "eagle-import:2,8")
      (libsource (lib "eagle-import") (part "MOUNT-HOLE2.8"))
    )
    (comp (ref "H2")
      (value "MOUNT-HOLE2.8")
      (footprint "eagle-import:2,8")
      (libsource (lib "eagle-import") (part "MOUNT-HOLE2.8"))
    )
    (comp (ref "H3")
      (value "MOUNT-HOLE2.8")
      (footprint "eagle-import:2,8")
      (libsource (lib "eagle-import") (part "MOUNT-HOLE2.8"))
    )
  )
  (nets
    (net (code "1") (name "+3V3") (class "Default")
      (node (ref "B2") (pin "1") (pinfunction "1_1") (pintype "passive"))
      (node (ref "B3") (pin "1") (pinfunction "1_1") (pintype "passive"))
      (node (ref "B4") (pin "1") (pinfunction "1_1") (pintype "passive"))
      (node (ref "BTN_NXT/1") (pin "1") (pinfunction "P_1") (pintype "passive"))
      (node (ref "BTN_RES/1") (pin "1") (pinfunction "P_1") (pintype "passive"))
      (node (ref "BTN_SCT/1") (pin "1") (pinfunction "P_1") (pintype "passive"))
      (node (ref "BT_RESET") (pin "3") (pinfunction "3_3") (pintype "passive"))
      (node (ref "BT_RESET") (pin "4") (pinfunction "4_4") (pintype "passive"))
      (node (ref "C6") (pin "1") (pinfunction "1_1") (pintype "passive"))
      (node (ref "C7") (pin "1") (pinfunction "1_1") (pintype "passive"))
      (node (ref "IC2") (pin "7") (pinfunction "SENSE_7") (pintype "input"))
      (node (ref "IC2") (pin "8") (pinfunction "VOUT_8") (pintype "power_in"))
      (node (ref "OK1") (pin "4") (pinfunction "COL_4") (pintype "passive"))
      (node (ref "OK2") (pin "4") (pinfunction "COL_4") (pintype "passive"))
      (node (ref "R1") (pin "1") (pinfunction "1_1") (pintype "passive"))
      (node (ref "R2") (pin "1") (pinfunction "1_1") (pintype "passive"))
      (node (ref "R25") (pin "2") (pinfunction "2_2") (pintype "passive"))
      (node (ref "R26") (pin "2") (pinfunction "2_2") (pintype "passive"))
      (node (ref "R29") (pin "2") (pinfunction "2_2") (pintype "passive"))
      (node (ref "R30") (pin "2") (pinfunction "2_2") (pintype "passive"))
      (node (ref "R7") (pin "2") (pinfunction "2_2") (pintype "passive"))
      (node (ref "SV1") (pin "1") (pinfunction "1_1") (pintype "passive"))
      (node (ref "SV5") (pin "1") (pinfunction "1_1") (pintype "passive"))
      (node (ref "SV6") (pin "1") (pinfunction "1_1") (pintype "passive"))
      (node (ref "SV7") (pin "7") (pinfunction "7_7") (pintype "passive"))
      (node (ref "U$3") (pin "3") (pinfunction "LV_3") (pintype "power_in"))
      (node (ref "U$4") (pin "4") (pinfunction "VOUT_4") (pintype "power_in"))
      (node (ref "U1") (pin "6") (pinfunction "S2_6") (pintype "passive"))
      (node (ref "V1") (pin "1") (pinfunction "G_1") (pintype "passive"))
      (node (ref "V2") (pin "1") (pinfunction "G_1") (pintype "passive"))
      (node (ref "V3") (pin "1") (pinfunction "G_1") (pintype "passive"))
      (node (ref "V4") (pin "1") (pinfunction "G_1") (pintype "passive"))
    )
    (net (code "2") (name "+5V") (class "Default")
      (node (ref "B1") (pin "2") (pinfunction "2_2") (pintype "passive"))
      (node (ref "BUZZER1") (pin "1") (pinfunction "KL_1") (pintype "passive"))
      (node (ref "BUZZER2") (pin "1") (pinfunction "KL_1") (pintype "passive"))
      (node (ref "C3") (pin "1") (pinfunction "1_1") (pintype "passive"))
      (node (ref "C4") (pin "1") (pinfunction "1_1") (pintype "passive"))
      (node (ref "C40") (pin "1") (pinfunction "1_1") (pintype "passive"))
      (node (ref "C41") (pin "1") (pinfunction "1_1") (pintype "passive"))
      (node (ref "C8") (pin "1") (pinfunction "1_1") (pintype "passive"))
      (node (ref "C9") (pin "1") (pinfunction "1_1") (pintype "passive"))
      (node (ref "IC2") (pin "1") (pinfunction "VIN_1") (pintype "power_in"))
      (node (ref "IC2") (pin "2") (pinfunction "VIN_2") (pintype "power_in"))
      (node (ref "IC2") (pin "3") (pinfunction "SHDN_3") (pintype "input"))
      (node (ref "J1") (pin "1") (pinfunction "VBUS_1") (pintype "bidirectional"))
      (node (ref "J2") (pin "1") (pinfunction "VBUS_1") (pintype "bidirectional"))
      (node (ref "R27") (pin "2") (pinfunction "2_2") (pintype "passive"))
      (node (ref "R28") (pin "2") (pinfunction "2_2") (pintype "passive"))
      (node (ref "R31") (pin "2") (pinfunction "2_2") (pintype "passive"))
      (node (ref "R32") (pin "2") (pinfunction "2_2") (pintype "passive"))
      (node (ref "SV2") (pin "1") (pinfunction "1_1") (pintype "passive"))
      (node (ref "SV2") (pin "2") (pinfunction "2_2") (pintype "passive"))
      (node (ref "SV3") (pin "1") (pinfunction "1_1") (pintype "passive"))
      (node (ref "SV7") (pin "2") (pinfunction "2_2") (pintype "passive"))
      (node (ref "U$3") (pin "9") (pinfunction "HV_9") (pintype "power_in"))
      (node (ref "U$4") (pin "2") (pinfunction "VIN_2") (pintype "power_in"))
      (node (ref "U2") (pin "10") (pinfunction "VDD_10") (pintype "power_in"))
    )
    (net (code "3") (name "BT_ACI0") (class "Default")
      (node (ref "U$1") (pin "3") (pinfunction "AIC0_3") (pintype "bidirectional"))
      (node (ref "U$2") (pin "ACI0") (pinfunction "AIC0_ACI0") (pintype "bidirectional"))
    )
    (net (code "4") (name "BT_LED0") (class "Default")
      (node (ref "LED2") (pin "C") (pinfunction "C_C") (pintype "passive"))
      (node (ref "U$1") (pin "30") (pinfunction "LED0_30") (pintype "bidirectional"))
    )
    (net (code "5") (name "BT_LED1") (class "Default")
      (node (ref "LED3") (pin "C") (pinfunction "C_C") (pintype "passive"))
      (node (ref "U$1") (pin "29") (pinfunction "LED1_29") (pintype "bidirectional"))
    )
    (net (code "6") (name "BT_MIC_BIAS") (class "Default")
      (node (ref "U$1") (pin "31") (pinfunction "MIC_BIAS_31") (pintype "bidirectional"))
      (node (ref "U$2") (pin "M_BIAS") (pinfunction "MIC_BIAS_M_BIAS") (pintype "bidirectional"))
    )
    (net (code "7") (name "BT_MIC_L+") (class "Default")
      (node (ref "U$1") (pin "32") (pinfunction "MIC_L+_32") (pintype "bidirectional"))
      (node (ref "U$2") (pin "MIC_L+") (pinfunction "MIC_L+_MIC_L+") (pintype "bidirectional"))
    )
    (net (code "8") (name "BT_MIC_L-") (class "Default")
      (node (ref "U$1") (pin "34") (pinfunction "MIC_L-_34") (pintype "bidirectional"))
      (node (ref "U$2") (pin "MIC_L-") (pinfunction "MIC_L-_MIC_L-") (pintype "bidirectional"))
    )
    (net (code "9") (name "BT_MIC_R+") (class "Default")
      (node (ref "U$1") (pin "33") (pinfunction "MIC_R+_33") (pintype "bidirectional"))
      (node (ref "U$2") (pin "MIC_R+") (pinfunction "MIC_R+_MIC_R+") (pintype "bidirectional"))
    )
    (net (code "10") (name "BT_MIC_R-") (class "Default")
      (node (ref "U$1") (pin "35") (pinfunction "MIC_R-_35") (pintype "bidirectional"))
      (node (ref "U$2") (pin "MIC_R-") (pinfunction "MIC_R-_MIC_R-") (pintype "bidirectional"))
    )
    (net (code "11") (name "BT_NEXT") (class "Default")
      (node (ref "U$1") (pin "6") (pinfunction "GPIO12_6") (pintype "bidirectional"))
      (node (ref "U$2") (pin "GPIO12") (pinfunction "GPIO12_GPIO12") (pintype "bidirectional"))
    )
    (net (code "12") (name "BT_PIO3") (class "Default")
      (node (ref "R4") (pin "2") (pinfunction "2_2") (pintype "passive"))
      (node (ref "R5") (pin "1") (pinfunction "1_1") (pintype "passive"))
      (node (ref "U$1") (pin "1") (pinfunction "GPIO3_1") (pintype "bidirectional"))
      (node (ref "U$2") (pin "GPIO3") (pinfunction "GPIO3_GPIO3") (pintype "bidirectional"))
    )
    (net (code "13") (name "BT_PIO4") (class "Default")
      (node (ref "BT_RESET") (pin "1") (pinfunction "1_1") (pintype "passive"))
      (node (ref "BT_RESET") (pin "2") (pinfunction "2_2") (pintype "passive"))
      (node (ref "R8") (pin "2") (pinfunction "2_2") (pintype "passive"))
      (node (ref "U$1") (pin "4") (pinfunction "GPIO4_4") (pintype "bidirectional"))
      (node (ref "U$2") (pin "GPIO4") (pinfunction "GPIO4_GPIO4") (pintype "bidirectional"))
    )
    (net (code "14") (name "BT_PLAY") (class "Default")
      (node (ref "U$1") (pin "7") (pinfunction "GPIO13_7") (pintype "bidirectional"))
      (node (ref "U$2") (pin "GPIO13") (pinfunction "GPIO13_GPIO13") (pintype "bidirectional"))
    )
    (net (code "15") (name "BT_PREV") (class "Default")
      (node (ref "U$1") (pin "8") (pinfunction "GPIO11_8") (pintype "bidirectional"))
      (node (ref "U$2") (pin "GPIO11") (pinfunction "GPIO11_GPIO11") (pintype "bidirectional"))
    )
    (net (code "16") (name "BT_SPK_L+") (class "Default")
      (node (ref "C32") (pin "1") (pinfunction "1_1") (pintype "passive"))
      (node (ref "U$1") (pin "40") (pinfunction "SPKR_L+_40") (pintype "bidirectional"))
      (node (ref "U$2") (pin "SPK_L+") (pinfunction "SPKR_L+_SPK_L+") (pintype "bidirectional"))
    )
    (net (code "17") (name "BT_SPK_L-") (class "Default")
      (node (ref "C31") (pin "1") (pinfunction "1_1") (pintype "passive"))
      (node (ref "U$1") (pin "38") (pinfunction "SPKR_L-_38") (pintype "bidirectional"))
      (node (ref "U$2") (pin "SPK_L-") (pinfunction "SPKR_L-_SPK_L-") (pintype "bidirectional"))
    )
    (net (code "18") (name "BT_SPK_R+") (class "Default")
      (node (ref "C33") (pin "1") (pinfunction "1_1") (pintype "passive"))
      (node (ref "U$1") (pin "39") (pinfunction "SPKR_R+_39") (pintype "bidirectional"))
      (node (ref "U$2") (pin "SPK_R+") (pinfunction "SPKR_R+_SPK_R+") (pintype "bidirectional"))
    )
    (net (code "19") (name "BT_SPK_R-") (class "Default")
      (node (ref "C34") (pin "1") (pinfunction "1_1") (pintype "passive"))
      (node (ref "U$1") (pin "37") (pinfunction "SPKR_R-_37") (pintype "bidirectional"))
      (node (ref "U$2") (pin "SPK_R-") (pinfunction "SPKR_R-_SPK_R-") (pintype "bidirectional"))
    )
    (net (code "20") (name "BT_USBD+") (class "Default")
      (node (ref "R7") (pin "1") (pinfunction "1_1") (pintype "passive"))
      (node (ref "U$1") (pin "12") (pinfunction "USBD+_12") (pintype "bidirectional"))
      (node (ref "U$2") (pin "USBD+") (pinfunction "USBD+_USBD+") (pintype "bidirectional"))
      (node (ref "USB2") (pin "D+") (pinfunction "D+_D+") (pintype "bidirectional"))
    )
    (net (code "21") (name "BT_USBD-") (class "Default")
      (node (ref "U$1") (pin "11") (pinfunction "USBD-_11") (pintype "bidirectional"))
      (node (ref "U$2") (pin "USBD-") (pinfunction "USBD-_USBD-") (pintype "bidirectional"))
      (node (ref "USB2") (pin "D-") (pinfunction "D-_D-") (pintype "bidirectional"))
    )
    (net (code "22") (name "BT_VCC") (class "Default")
      (node (ref "C23") (pin "1") (pinfunction "1_1") (pintype "passive"))
      (node (ref "C30") (pin "1") (pinfunction "1_1") (pintype "passive"))
      (node (ref "R10") (pin "2") (pinfunction "2_2") (pintype "passive"))
      (node (ref "R9") (pin "2") (pinfunction "2_2") (pintype "passive"))
      (node (ref "U$1") (pin "20") (pinfunction "VDD_20") (pintype "bidirectional"))
      (node (ref "U$2") (pin "3V3") (pinfunction "VDD_3V3") (pintype "bidirectional"))
      (node (ref "U1") (pin "5") (pinfunction "D_5") (pintype "passive"))
    )
    (net (code "23") (name "BT_VOL_DOWN") (class "Default")
      (node (ref "U$1") (pin "9") (pinfunction "GPIO10_9") (pintype "bidirectional"))
      (node (ref "U$2") (pin "GPIO10") (pinfunction "GPIO10_GPIO10") (pintype "bidirectional"))
    )
    (net (code "24") (name "BT_VOL_UP") (class "Default")
      (node (ref "U$1") (pin "5") (pinfunction "GPIO5_5") (pintype "bidirectional"))
      (node (ref "U$2") (pin "GPIO5") (pinfunction "GPIO5_GPIO5") (pintype "bidirectional"))
    )
    (net (code "25") (name "GND") (class "Default")
      (node (ref "AUDIO") (pin "3") (pinfunction "3_3") (pintype "passive"))
      (node (ref "C1") (pin "2") (pinfunction "2_2") (pintype "passive"))
      (node (ref "C10") (pin "2") (pinfunction "2_2") (pintype "passive"))
      (node (ref "C11") (pin "2") (pinfunction "2_2") (pintype "passive"))
      (node (ref "C12") (pin "2") (pinfunction "2_2") (pintype "passive"))
      (node (ref "C13") (pin "2") (pinfunction "2_2") (pintype "passive"))
      (node (ref "C14") (pin "2") (pinfunction "2_2") (pintype "passive"))
      (node (ref "C15") (pin "2") (pinfunction "2_2") (pintype "passive"))
      (node (ref "C16") (pin "2") (pinfunction "2_2") (pintype "passive"))
      (node (ref "C17") (pin "2") (pinfunction "2_2") (pintype "passive"))
      (node (ref "C18") (pin "1") (pinfunction "1_1") (pintype "passive"))
      (node (ref "C19") (pin "1") (pinfunction "1_1") (pintype "passive"))
      (node (ref "C2") (pin "2") (pinfunction "2_2") (pintype "passive"))
      (node (ref "C20") (pin "2") (pinfunction "2_2") (pintype "passive"))
      (node (ref "C21") (pin "2") (pinfunction "2_2") (pintype "passive"))
      (node (ref "C22") (pin "2") (pinfunction "2_2") (pintype "passive"))
      (node (ref "C23") (pin "2") (pinfunction "2_2") (pintype "passive"))
      (node (ref "C24") (pin "2") (pinfunction "2_2") (pintype "passive"))
      (node (ref "C25") (pin "2") (pinfunction "2_2") (pintype "passive"))
      (node (ref "C26") (pin "2") (pinfunction "2_2") (pintype "passive"))
      (node (ref "C27") (pin "2") (pinfunction "2_2") (pintype "passive"))
      (node (ref "C28") (pin "2") (pinfunction "2_2") (pintype "passive"))
      (node (ref "C29") (pin "2") (pinfunction "2_2") (pintype "passive"))
      (node (ref "C3") (pin "2") (pinfunction "2_2") (pintype "passive"))
      (node (ref "C30") (pin "2") (pinfunction "2_2") (pintype "passive"))
      (node (ref "C35") (pin "1") (pinfunction "1_1") (pintype "passive"))
      (node (ref "C4") (pin "2") (pinfunction "2_2") (pintype "passive"))
      (node (ref "C40") (pin "2") (pinfunction "2_2") (pintype "passive"))
      (node (ref "C41") (pin "2") (pinfunction "2_2") (pintype "passive"))
      (node (ref "C5") (pin "2") (pinfunction "2_2") (pintype "passive"))
      (node (ref "C6") (pin "2") (pinfunction "2_2") (pintype "passive"))
      (node (ref "C7") (pin "2") (pinfunction "2_2") (pintype "passive"))
      (node (ref "C8") (pin "2") (pinfunction "2_2") (pintype "passive"))
      (node (ref "C9") (pin "2") (pinfunction "2_2") (pintype "passive"))
      (node (ref "D1") (pin "A") (pinfunction "A_A") (pintype "passive"))
      (node (ref "DEBUG") (pin "3") (pinfunction "3_3") (pintype "passive"))
      (node (ref "IC1") (pin "12") (pinfunction "VSSA/VREF-_12") (pintype "power_in"))
      (node (ref "IC1") (pin "18") (pinfunction "VSS1_18") (pintype "power_in"))
      (node (ref "IC1") (pin "3") (pinfunction "PC14-OSC32_IN_3") (pintype "input"))
      (node (ref "IC1") (pin "31") (pinfunction "VSS2_31") (pintype "power_in"))
      (node (ref "IC1") (pin "4") (pinfunction "PC15-OSC32_OUT_4") (pintype "output"))
      (node (ref "IC1") (pin "47") (pinfunction "VSS3_47") (pintype "power_in"))
      (node (ref "IC1") (pin "60") (pinfunction "BOOT0_60") (pintype "bidirectional"))
      (node (ref "IC1") (pin "63") (pinfunction "VSS4_63") (pintype "power_in"))
      (node (ref "IC2") (pin "4") (pinfunction "GND_4") (pintype "passive"))
      (node (ref "J1") (pin "4") (pinfunction "GND_4") (pintype "bidirectional"))
      (node (ref "J1") (pin "Z1") (pinfunction "Z1_Z1") (pintype "bidirectional"))
      (node (ref "J1") (pin "Z2") (pinfunction "Z2_Z2") (pintype "bidirectional"))
      (node (ref "J2") (pin "4") (pinfunction "GND_4") (pintype "bidirectional"))
      (node (ref "J2") (pin "Z1") (pinfunction "Z1_Z1") (pintype "bidirectional"))
      (node (ref "J2") (pin "Z2") (pinfunction "Z2_Z2") (pintype "bidirectional"))
      (node (ref "LED1") (pin "C") (pinfunction "C_C") (pintype "passive"))
      (node (ref "R13") (pin "1") (pinfunction "1_1") (pintype "passive"))
      (node (ref "R15") (pin "1") (pinfunction "1_1") (pintype "passive"))
      (node (ref "R17") (pin "1") (pinfunction "1_1") (pintype "passive"))
      (node (ref "R19") (pin "1") (pinfunction "1_1") (pintype "passive"))
      (node (ref "R21") (pin "1") (pinfunction "1_1") (pintype "passive"))
      (node (ref "R22") (pin "1") (pinfunction "1_1") (pintype "passive"))
      (node (ref "R24") (pin "1") (pinfunction "1_1") (pintype "passive"))
      (node (ref "R34") (pin "2") (pinfunction "2_2") (pintype "passive"))
      (node (ref "R36") (pin "2") (pinfunction "2_2") (pintype "passive"))
      (node (ref "R5") (pin "2") (pinfunction "2_2") (pintype "passive"))
      (node (ref "R8") (pin "1") (pinfunction "1_1") (pintype "passive"))
      (node (ref "RESET") (pin "1") (pinfunction "1_1") (pintype "passive"))
      (node (ref "RESET") (pin "2") (pinfunction "2_2") (pintype "passive"))
      (node (ref "SV1") (pin "4") (pinfunction "4_4") (pintype "passive"))
      (node (ref "SV2") (pin "7") (pinfunction "7_7") (pintype "passive"))
      (node (ref "SV2") (pin "8") (pinfunction "8_8") (pintype "passive"))
      (node (ref "SV3") (pin "2") (pinfunction "2_2") (pintype "passive"))
      (node (ref "SV5") (pin "4") (pinfunction "4_4") (pintype "passive"))
      (node (ref "SV6") (pin "2") (pinfunction "2_2") (pintype "passive"))
      (node (ref "SV7") (pin "1") (pinfunction "1_1") (pintype "passive"))
      (node (ref "SV7") (pin "8") (pinfunction "8_8") (pintype "passive"))
      (node (ref "U$1") (pin "36") (pinfunction "AGND_36") (pintype "bidirectional"))
      (node (ref "U$1") (pin "G1") (pinfunction "GND9_G1") (pintype "bidirectional"))
      (node (ref "U$1") (pin "G2") (pinfunction "GND8_G2") (pintype "bidirectional"))
      (node (ref "U$1") (pin "G3") (pinfunction "GND7_G3") (pintype "bidirectional"))
      (node (ref "U$1") (pin "G4") (pinfunction "GND6_G4") (pintype "bidirectional"))
      (node (ref "U$1") (pin "RFG1") (pinfunction "GND_RFG1") (pintype "bidirectional"))
      (node (ref "U$1") (pin "RFG2") (pinfunction "GND1_RFG2") (pintype "bidirectional"))
      (node (ref "U$1") (pin "RFG3") (pinfunction "GND2_RFG3") (pintype "bidirectional"))
      (node (ref "U$1") (pin "RFG4") (pinfunction "GND3_RFG4") (pintype "bidirectional"))
      (node (ref "U$1") (pin "RFG5") (pinfunction "GND4_RFG5") (pintype "bidirectional"))
      (node (ref "U$1") (pin "RFG6") (pinfunction "GND5_RFG6") (pintype "bidirectional"))
      (node (ref "U$2") (pin "GND") (pinfunction "GND_GND") (pintype "bidirectional"))
      (node (ref "U$3") (pin "10") (pinfunction "GND_10") (pintype "power_in"))
      (node (ref "U$3") (pin "4") (pinfunction "GND0_4") (pintype "power_in"))
      (node (ref "U$4") (pin "1") (pinfunction "GND1_1") (pintype "power_in"))
      (node (ref "U$4") (pin "3") (pinfunction "GND2_3") (pintype "power_in"))
      (node (ref "U1") (pin "3") (pinfunction "GND_3") (pintype "power_in"))
      (node (ref "U1") (pin "4") (pinfunction "S1_4") (pintype "passive"))
      (node (ref "U2") (pin "11") (pinfunction "EP_11") (pintype "bidirectional"))
      (node (ref "U2") (pin "5") (pinfunction "GND_5") (pintype "power_in"))
      (node (ref "U2") (pin "6") (pinfunction "SD_6") (pintype "input"))
      (node (ref "U2") (pin "PAD_1") (pinfunction "EP_PAD_1") (pintype "bidirectional"))
      (node (ref "U2") (pin "PAD_2") (pinfunction "EP_PAD_2") (pintype "bidirectional"))
      (node (ref "U2") (pin "PAD_3") (pinfunction "EP_PAD_3") (pintype "bidirectional"))
      (node (ref "U2") (pin "PAD_4") (pinfunction "EP_PAD_4") (pintype "bidirectional"))
      (node (ref "U2") (pin "PAD_5") (pinfunction "EP_PAD_5") (pintype "bidirectional"))
      (node (ref "USB1") (pin "GND") (pinfunction "GND_GND") (pintype "power_in"))
      (node (ref "USB1") (pin "SLD1") (pinfunction "SHIELD_SLD1") (pintype "bidirectional"))
      (node (ref "USB1") (pin "SLD2") (pinfunction "SHIELD2_SLD2") (pintype "bidirectional"))
      (node (ref "USB1") (pin "SLD3") (pinfunction "SHIELD3_SLD3") (pintype "bidirectional"))
      (node (ref "USB1") (pin "SLD4") (pinfunction "SHIELD4_SLD4") (pintype "bidirectional"))
      (node (ref "USB1") (pin "SLD5") (pinfunction "SHIELD5_SLD5") (pintype "bidirectional"))
      (node (ref "USB1") (pin "SLD6") (pinfunction "SHIELD6_SLD6") (pintype "bidirectional"))
      (node (ref "USB2") (pin "GND") (pinfunction "GND_GND") (pintype "power_in"))
      (node (ref "USB2") (pin "SLD1") (pinfunction "SHIELD_SLD1") (pintype "bidirectional"))
      (node (ref "USB2") (pin "SLD2") (pinfunction "SHIELD2_SLD2") (pintype "bidirectional"))
      (node (ref "USB2") (pin "SLD3") (pinfunction "SHIELD3_SLD3") (pintype "bidirectional"))
      (node (ref "USB2") (pin "SLD4") (pinfunction "SHIELD4_SLD4") (pintype "bidirectional"))
      (node (ref "USB2") (pin "SLD5") (pinfunction "SHIELD5_SLD5") (pintype "bidirectional"))
      (node (ref "USB2") (pin "SLD6") (pinfunction "SHIELD6_SLD6") (pintype "bidirectional"))
    )
    (net (code "26") (name "I2C_SCL_5V") (class "Default")
      (node (ref "R31") (pin "1") (pinfunction "1_1") (pintype "passive"))
      (node (ref "SV7") (pin "3") (pinfunction "3_3") (pintype "passive"))
      (node (ref "U$3") (pin "11") (pinfunction "HV3_11") (pintype "bidirectional"))
      (node (ref "V3") (pin "3") (pinfunction "D_3") (pintype "passive"))
    )
    (net (code "27") (name "I2C_SDA_5V") (class "Default")
      (node (ref "R32") (pin "1") (pinfunction "1_1") (pintype "passive"))
      (node (ref "SV7") (pin "4") (pinfunction "4_4") (pintype "passive"))
      (node (ref "U$3") (pin "12") (pinfunction "HV4_12") (pintype "bidirectional"))
      (node (ref "V4") (pin "3") (pinfunction "D_3") (pintype "passive"))
    )
    (net (code "28") (name "LCD_I2C_SCL_5V") (class "Default")
      (node (ref "R28") (pin "1") (pinfunction "1_1") (pintype "passive"))
      (node (ref "SV3") (pin "4") (pinfunction "4_4") (pintype "passive"))
      (node (ref "U$3") (pin "7") (pinfunction "HV1_7") (pintype "bidirectional"))
      (node (ref "V2") (pin "3") (pinfunction "D_3") (pintype "passive"))
    )
    (net (code "29") (name "LCD_I2C_SDA_5V") (class "Default")
      (node (ref "R27") (pin "1") (pinfunction "1_1") (pintype "passive"))
      (node (ref "SV3") (pin "3") (pinfunction "3_3") (pintype "passive"))
      (node (ref "U$3") (pin "8") (pinfunction "HV2_8") (pintype "bidirectional"))
      (node (ref "V1") (pin "3") (pinfunction "D_3") (pintype "passive"))
    )
    (net (code "30") (name "MCU_BT_ENABLE") (class "Default")
      (node (ref "IC1") (pin "41") (pinfunction "PA8_41") (pintype "bidirectional"))
      (node (ref "U1") (pin "1") (pinfunction "IN_1") (pintype "input"))
    )
    (net (code "31") (name "MCU_BT_INT") (class "Default")
      (node (ref "IC1") (pin "39") (pinfunction "PC8_39") (pintype "bidirectional"))
      (node (ref "U$1") (pin "2") (pinfunction "GPIO2_2") (pintype "bidirectional"))
      (node (ref "U$2") (pin "GPIO2") (pinfunction "GPIO2_GPIO2") (pintype "bidirectional"))
    )
    (net (code "32") (name "MCU_BT_PWR_EN") (class "Default")
      (node (ref "IC1") (pin "40") (pinfunction "PC9_40") (pintype "bidirectional"))
      (node (ref "U$1") (pin "19") (pinfunction "PWREN_19") (pintype "bidirectional"))
      (node (ref "U$2") (pin "PWR_EN") (pinfunction "PWREN_PWR_EN") (pintype "bidirectional"))
    )
    (net (code "33") (name "MCU_BT_RX") (class "Default")
      (node (ref "IC1") (pin "42") (pinfunction "PA9_42") (pintype "bidirectional"))
      (node (ref "U$1") (pin "16") (pinfunction "UART_RX_16") (pintype "bidirectional"))
      (node (ref "U$2") (pin "UART_RX") (pinfunction "UART_RX_UART_RX") (pintype "bidirectional"))
    )
    (net (code "34") (name "MCU_BT_TX") (class "Default")
      (node (ref "IC1") (pin "43") (pinfunction "PA10_43") (pintype "bidirectional"))
      (node (ref "U$1") (pin "15") (pinfunction "UART_TX_15") (pintype "bidirectional"))
      (node (ref "U$2") (pin "UART_TX") (pinfunction "UART_TX_UART_TX") (pintype "bidirectional"))
    )
    (net (code "35") (name "MCU_BT_~{CMD_MODE}") (class "Default")
      (node (ref "IC1") (pin "38") (pinfunction "PC7_38") (pintype "bidirectional"))
      (node (ref "U$1") (pin "10") (pinfunction "GPIO9_10") (pintype "bidirectional"))
      (node (ref "U$2") (pin "GPIO9") (pinfunction "GPIO9_GPIO9") (pintype "bidirectional"))
    )
    (net (code "36") (name "MCU_BUTTON_NEXT") (class "Default")
      (node (ref "C25") (pin "1") (pinfunction "1_1") (pintype "passive"))
      (node (ref "IC1") (pin "52") (pinfunction "PC11_52") (pintype "bidirectional"))
      (node (ref "R14") (pin "2") (pinfunction "2_2") (pintype "passive"))
    )
    (net (code "37") (name "MCU_BUTTON_RES") (class "Default")
      (node (ref "C27") (pin "1") (pinfunction "1_1") (pintype "passive"))
      (node (ref "IC1") (pin "50") (pinfunction "PA15_50") (pintype "bidirectional"))
      (node (ref "R18") (pin "2") (pinfunction "2_2") (pintype "passive"))
    )
    (net (code "38") (name "MCU_BUTTON_SELECT") (class "Default")
      (node (ref "C26") (pin "1") (pinfunction "1_1") (pintype "passive"))
      (node (ref "IC1") (pin "51") (pinfunction "PC10_51") (pintype "bidirectional"))
      (node (ref "R16") (pin "2") (pinfunction "2_2") (pintype "passive"))
    )
    (net (code "39") (name "MCU_BUZZER1") (class "Default")
      (node (ref "C28") (pin "1") (pinfunction "1_1") (pintype "passive"))
      (node (ref "IC1") (pin "53") (pinfunction "PC12_53") (pintype "bidirectional"))
      (node (ref "R20") (pin "1") (pinfunction "1_1") (pintype "passive"))
    )
    (net (code "40") (name "MCU_BUZZER2") (class "Default")
      (node (ref "C29") (pin "1") (pinfunction "1_1") (pintype "passive"))
      (node (ref "IC1") (pin "54") (pinfunction "PD2_54") (pintype "bidirectional"))
      (node (ref "R23") (pin "1") (pinfunction "1_1") (pintype "passive"))
    )
    (net (code "41") (name "MCU_DEBUG_RX") (class "Default")
      (node (ref "DEBUG") (pin "1") (pinfunction "1_1") (pintype "passive"))
      (node (ref "IC1") (pin "17") (pinfunction "PA3_17") (pintype "bidirectional"))
    )
    (net (code "42") (name "MCU_DEBUG_TX") (class "Default")
      (node (ref "DEBUG") (pin "2") (pinfunction "2_2") (pintype "passive"))
      (node (ref "IC1") (pin "16") (pinfunction "PA2_16") (pintype "bidirectional"))
    )
    (net (code "43") (name "MCU_I2C2_SCL") (class "Default")
      (node (ref "IC1") (pin "29") (pinfunction "PB10_29") (pintype "bidirectional"))
      (node (ref "R29") (pin "1") (pinfunction "1_1") (pintype "passive"))
      (node (ref "SV7") (pin "6") (pinfunction "6_6") (pintype "passive"))
      (node (ref "U$3") (pin "5") (pinfunction "LV3_5") (pintype "bidirectional"))
      (node (ref "V3") (pin "2") (pinfunction "S_2") (pintype "passive"))
    )
    (net (code "44") (name "MCU_I2C2_SDA") (class "Default")
      (node (ref "IC1") (pin "55") (pinfunction "PB3_55") (pintype "bidirectional"))
      (node (ref "R30") (pin "1") (pinfunction "1_1") (pintype "passive"))
      (node (ref "SV7") (pin "5") (pinfunction "5_5") (pintype "passive"))
      (node (ref "U$3") (pin "6") (pinfunction "LV4_6") (pintype "bidirectional"))
      (node (ref "V4") (pin "2") (pinfunction "S_2") (pintype "passive"))
    )
    (net (code "45") (name "MCU_LCD_I2C_SCL") (class "Default")
      (node (ref "IC1") (pin "58") (pinfunction "PB6_58") (pintype "bidirectional"))
      (node (ref "R26") (pin "1") (pinfunction "1_1") (pintype "passive"))
      (node (ref "SV3") (pin "6") (pinfunction "6_6") (pintype "passive"))
      (node (ref "U$3") (pin "1") (pinfunction "LV1_1") (pintype "bidirectional"))
      (node (ref "V2") (pin "2") (pinfunction "S_2") (pintype "passive"))
    )
    (net (code "46") (name "MCU_LCD_I2C_SDA") (class "Default")
      (node (ref "IC1") (pin "59") (pinfunction "PB7_59") (pintype "bidirectional"))
      (node (ref "R25") (pin "1") (pinfunction "1_1") (pintype "passive"))
      (node (ref "SV3") (pin "5") (pinfunction "5_5") (pintype "passive"))
      (node (ref "U$3") (pin "2") (pinfunction "LV2_2") (pintype "bidirectional"))
      (node (ref "V1") (pin "2") (pinfunction "S_2") (pintype "passive"))
    )
    (net (code "47") (name "MCU_SONIC1_ECHO") (class "Default")
      (node (ref "IC1") (pin "26") (pinfunction "PB0_26") (pintype "bidirectional"))
      (node (ref "R33") (pin "2") (pinfunction "2_2") (pintype "passive"))
      (node (ref "R34") (pin "1") (pinfunction "1_1") (pintype "passive"))
    )
    (net (code "48") (name "MCU_SONIC1_TRIG") (class "Default")
      (node (ref "IC1") (pin "25") (pinfunction "PC5_25") (pintype "bidirectional"))
      (node (ref "SV2") (pin "3") (pinfunction "3_3") (pintype "passive"))
    )
    (net (code "49") (name "MCU_SONIC2_ECHO") (class "Default")
      (node (ref "IC1") (pin "27") (pinfunction "PB1_27") (pintype "bidirectional"))
      (node (ref "R35") (pin "2") (pinfunction "2_2") (pintype "passive"))
      (node (ref "R36") (pin "1") (pinfunction "1_1") (pintype "passive"))
    )
    (net (code "50") (name "MCU_SONIC2_TRIG") (class "Default")
      (node (ref "IC1") (pin "28") (pinfunction "PB2_28") (pintype "bidirectional"))
      (node (ref "SV2") (pin "4") (pinfunction "4_4") (pintype "passive"))
    )
    (net (code "51") (name "MCU_SPI_MISO") (class "Default")
      (node (ref "IC1") (pin "22") (pinfunction "PA6_22") (pintype "bidirectional"))
      (node (ref "SV6") (pin "3") (pinfunction "3_3") (pintype "passive"))
    )
    (net (code "52") (name "MCU_SPI_MOSI") (class "Default")
      (node (ref "IC1") (pin "23") (pinfunction "PA7_23") (pintype "bidirectional"))
      (node (ref "SV6") (pin "4") (pinfunction "4_4") (pintype "passive"))
    )
    (net (code "53") (name "MCU_SPI_NSS") (class "Default")
      (node (ref "IC1") (pin "20") (pinfunction "PA4_20") (pintype "bidirectional"))
      (node (ref "SV6") (pin "6") (pinfunction "6_6") (pintype "passive"))
    )
    (net (code "54") (name "MCU_SPI_SCK") (class "Default")
      (node (ref "IC1") (pin "21") (pinfunction "PA5_21") (pintype "bidirectional"))
      (node (ref "SV6") (pin "5") (pinfunction "5_5") (pintype "passive"))
    )
    (net (code "55") (name "MCU_SWCLK") (class "Default")
      (node (ref "IC1") (pin "49") (pinfunction "PA14_49") (pintype "bidirectional"))
      (node (ref "SV1") (pin "3") (pinfunction "3_3") (pintype "passive"))
    )
    (net (code "56") (name "MCU_SWDIO") (class "Default")
      (node (ref "IC1") (pin "46") (pinfunction "PA13_46") (pintype "bidirectional"))
      (node (ref "SV1") (pin "2") (pinfunction "2_2") (pintype "passive"))
    )
    (net (code "57") (name "MCU_UART_RX") (class "Default")
      (node (ref "IC1") (pin "45") (pinfunction "PA12_45") (pintype "bidirectional"))
      (node (ref "SV5") (pin "2") (pinfunction "2_2") (pintype "passive"))
    )
    (net (code "58") (name "MCU_UART_TX") (class "Default")
      (node (ref "IC1") (pin "44") (pinfunction "PA11_44") (pintype "bidirectional"))
      (node (ref "SV5") (pin "3") (pinfunction "3_3") (pintype "passive"))
    )
    (net (code "59") (name "Net-(AUDIO-Pad1)") (class "Default")
      (node (ref "AUDIO") (pin "1") (pinfunction "1_1") (pintype "passive"))
      (node (ref "C36") (pin "2") (pinfunction "2_2") (pintype "passive"))
      (node (ref "C37") (pin "2") (pinfunction "2_2") (pintype "passive"))
    )
    (net (code "60") (name "Net-(AUDIO-Pad2)") (class "Default")
      (node (ref "AUDIO") (pin "2") (pinfunction "2_2") (pintype "passive"))
      (node (ref "C38") (pin "2") (pinfunction "2_2") (pintype "passive"))
      (node (ref "C39") (pin "2") (pinfunction "2_2") (pintype "passive"))
    )
    (net (code "61") (name "Net-(B1-Pad1)") (class "Default")
      (node (ref "B1") (pin "1") (pinfunction "1_1") (pintype "passive"))
      (node (ref "C1") (pin "1") (pinfunction "1_1") (pintype "passive"))
      (node (ref "C2") (pin "1") (pinfunction "1_1") (pintype "passive"))
      (node (ref "D1") (pin "C") (pinfunction "C_C") (pintype "passive"))
      (node (ref "USB1") (pin "VBUS") (pinfunction "VBUS_VBUS") (pintype "power_in"))
    )
    (net (code "62") (name "Net-(BUZZER1B-KL)") (class "Default")
      (node (ref "BUZZER1") (pin "2") (pinfunction "KL_2") (pintype "passive"))
      (node (ref "OK1") (pin "1") (pinfunction "A_1") (pintype "passive"))
    )
    (net (code "63") (name "Net-(BUZZER2B-KL)") (class "Default")
      (node (ref "BUZZER2") (pin "2") (pinfunction "KL_2") (pintype "passive"))
      (node (ref "OK2") (pin "1") (pinfunction "A_1") (pintype "passive"))
    )
    (net (code "64") (name "Net-(C24-Pad1)") (class "Default")
      (node (ref "C24") (pin "1") (pinfunction "1_1") (pintype "passive"))
      (node (ref "R4") (pin "1") (pinfunction "1_1") (pintype "passive"))
      (node (ref "USB2") (pin "VBUS") (pinfunction "VBUS_VBUS") (pintype "power_in"))
    )
    (net (code "65") (name "Net-(C31-Pad2)") (class "Default")
      (node (ref "C31") (pin "2") (pinfunction "2_2") (pintype "passive"))
      (node (ref "R6") (pin "1") (pinfunction "1_1") (pintype "passive"))
    )
    (net (code "66") (name "Net-(C32-Pad2)") (class "Default")
      (node (ref "C32") (pin "2") (pinfunction "2_2") (pintype "passive"))
      (node (ref "R37") (pin "1") (pinfunction "1_1") (pintype "passive"))
    )
    (net (code "67") (name "Net-(C33-Pad2)") (class "Default")
      (node (ref "C33") (pin "2") (pinfunction "2_2") (pintype "passive"))
      (node (ref "R38") (pin "1") (pinfunction "1_1") (pintype "passive"))
    )
    (net (code "68") (name "Net-(C34-Pad2)") (class "Default")
      (node (ref "C34") (pin "2") (pinfunction "2_2") (pintype "passive"))
      (node (ref "R39") (pin "1") (pinfunction "1_1") (pintype "passive"))
    )
    (net (code "69") (name "Net-(IC1-VCAP1)") (class "Default")
      (node (ref "C15") (pin "1") (pinfunction "1_1") (pintype "passive"))
      (node (ref "IC1") (pin "30") (pinfunction "VCAP1_30") (pintype "bidirectional"))
    )
    (net (code "70") (name "Net-(IC2-CDELAY)") (class "Default")
      (node (ref "C5") (pin "1") (pinfunction "1_1") (pintype "passive"))
      (node (ref "IC2") (pin "6") (pinfunction "CDELAY_6") (pintype "input"))
    )
    (net (code "71") (name "Net-(IC2-PWRGD)") (class "Default")
      (node (ref "IC2") (pin "5") (pinfunction "PWRGD_5") (pintype "output"))
      (node (ref "R1") (pin "2") (pinfunction "2_2") (pintype "passive"))
    )
    (net (code "72") (name "Net-(LED1-PadA)") (class "Default")
      (node (ref "LED1") (pin "A") (pinfunction "A_A") (pintype "passive"))
      (node (ref "R2") (pin "2") (pinfunction "2_2") (pintype "passive"))
    )
    (net (code "73") (name "Net-(LED2-PadA)") (class "Default")
      (node (ref "LED2") (pin "A") (pinfunction "A_A") (pintype "passive"))
      (node (ref "R10") (pin "1") (pinfunction "1_1") (pintype "passive"))
    )
    (net (code "74") (name "Net-(LED3-PadA)") (class "Default")
      (node (ref "LED3") (pin "A") (pinfunction "A_A") (pintype "passive"))
      (node (ref "R9") (pin "1") (pinfunction "1_1") (pintype "passive"))
    )
    (net (code "75") (name "Net-(NXT-P)") (class "Default")
      (node (ref "NXT") (pin "1") (pinfunction "P_1") (pintype "passive"))
      (node (ref "R13") (pin "2") (pinfunction "2_2") (pintype "passive"))
      (node (ref "R14") (pin "1") (pinfunction "1_1") (pintype "passive"))
    )
    (net (code "76") (name "Net-(OK1-C)") (class "Default")
      (node (ref "OK1") (pin "2") (pinfunction "C_2") (pintype "passive"))
      (node (ref "R21") (pin "2") (pinfunction "2_2") (pintype "passive"))
    )
    (net (code "77") (name "Net-(OK1-EMIT)") (class "Default")
      (node (ref "OK1") (pin "3") (pinfunction "EMIT_3") (pintype "passive"))
      (node (ref "R19") (pin "2") (pinfunction "2_2") (pintype "passive"))
      (node (ref "R20") (pin "2") (pinfunction "2_2") (pintype "passive"))
    )
    (net (code "78") (name "Net-(OK2-C)") (class "Default")
      (node (ref "OK2") (pin "2") (pinfunction "C_2") (pintype "passive"))
      (node (ref "R24") (pin "2") (pinfunction "2_2") (pintype "passive"))
    )
    (net (code "79") (name "Net-(OK2-EMIT)") (class "Default")
      (node (ref "OK2") (pin "3") (pinfunction "EMIT_3") (pintype "passive"))
      (node (ref "R22") (pin "2") (pinfunction "2_2") (pintype "passive"))
      (node (ref "R23") (pin "2") (pinfunction "2_2") (pintype "passive"))
    )
    (net (code "80") (name "Net-(R33-Pad1)") (class "Default")
      (node (ref "R33") (pin "1") (pinfunction "1_1") (pintype "passive"))
      (node (ref "SV2") (pin "5") (pinfunction "5_5") (pintype "passive"))
    )
    (net (code "81") (name "Net-(R35-Pad1)") (class "Default")
      (node (ref "R35") (pin "1") (pinfunction "1_1") (pintype "passive"))
      (node (ref "SV2") (pin "6") (pinfunction "6_6") (pintype "passive"))
    )
    (net (code "82") (name "Net-(RES-P)") (class "Default")
      (node (ref "R17") (pin "2") (pinfunction "2_2") (pintype "passive"))
      (node (ref "R18") (pin "1") (pinfunction "1_1") (pintype "passive"))
      (node (ref "RES") (pin "1") (pinfunction "P_1") (pintype "passive"))
    )
    (net (code "83") (name "Net-(SCT-P)") (class "Default")
      (node (ref "R15") (pin "2") (pinfunction "2_2") (pintype "passive"))
      (node (ref "R16") (pin "1") (pinfunction "1_1") (pintype "passive"))
      (node (ref "SCT") (pin "1") (pinfunction "P_1") (pintype "passive"))
    )
    (net (code "84") (name "Net-(U1-VDD)") (class "Default")
      (node (ref "B4") (pin "2") (pinfunction "2_2") (pintype "passive"))
      (node (ref "C22") (pin "1") (pinfunction "1_1") (pintype "passive"))
      (node (ref "U1") (pin "2") (pinfunction "VDD_2") (pintype "power_in"))
    )
    (net (code "85") (name "Net-(U2-BYPASS)") (class "Default")
      (node (ref "C35") (pin "2") (pinfunction "2_2") (pintype "passive"))
      (node (ref "R40") (pin "1") (pinfunction "1_1") (pintype "passive"))
      (node (ref "R41") (pin "1") (pinfunction "1_1") (pintype "passive"))
      (node (ref "U2") (pin "4") (pinfunction "BYPASS_4") (pintype "input"))
    )
    (net (code "86") (name "Net-(U2-IN1+)") (class "Default")
      (node (ref "R37") (pin "2") (pinfunction "2_2") (pintype "passive"))
      (node (ref "R41") (pin "2") (pinfunction "2_2") (pintype "passive"))
      (node (ref "U2") (pin "3") (pinfunction "IN1+_3") (pintype "input"))
    )
    (net (code "87") (name "Net-(U2-IN1-)") (class "Default")
      (node (ref "R42") (pin "1") (pinfunction "1_1") (pintype "passive"))
      (node (ref "R6") (pin "2") (pinfunction "2_2") (pintype "passive"))
      (node (ref "U2") (pin "2") (pinfunction "IN1-_2") (pintype "input"))
    )
    (net (code "88") (name "Net-(U2-IN2+)") (class "Default")
      (node (ref "R38") (pin "2") (pinfunction "2_2") (pintype "passive"))
      (node (ref "R40") (pin "2") (pinfunction "2_2") (pintype "passive"))
      (node (ref "U2") (pin "7") (pinfunction "IN2+_7") (pintype "input"))
    )
    (net (code "89") (name "Net-(U2-IN2-)") (class "Default")
      (node (ref "R39") (pin "2") (pinfunction "2_2") (pintype "passive"))
      (node (ref "R43") (pin "1") (pinfunction "1_1") (pintype "passive"))
      (node (ref "U2") (pin "8") (pinfunction "IN2-_8") (pintype "input"))
    )
    (net (code "90") (name "Net-(U2-VO1)") (class "Default")
      (node (ref "C36") (pin "1") (pinfunction "1_1") (pintype "passive"))
      (node (ref "C37") (pin "1") (pinfunction "1_1") (pintype "passive"))
      (node (ref "R42") (pin "2") (pinfunction "2_2") (pintype "passive"))
      (node (ref "U2") (pin "1") (pinfunction "VO1_1") (pintype "output"))
    )
    (net (code "91") (name "Net-(U2-VO2)") (class "Default")
      (node (ref "C38") (pin "1") (pinfunction "1_1") (pintype "passive"))
      (node (ref "C39") (pin "1") (pinfunction "1_1") (pintype "passive"))
      (node (ref "R43") (pin "2") (pinfunction "2_2") (pintype "passive"))
      (node (ref "U2") (pin "9") (pinfunction "VO2_9") (pintype "output"))
    )
    (net (code "92") (name "OSC_IN") (class "Default")
      (node (ref "C18") (pin "2") (pinfunction "2_2") (pintype "passive"))
      (node (ref "IC1") (pin "5") (pinfunction "PH0-OSC_IN_5") (pintype "input"))
      (node (ref "Q1") (pin "2") (pinfunction "2_2") (pintype "bidirectional"))
    )
    (net (code "93") (name "OSC_OUT") (class "Default")
      (node (ref "C19") (pin "2") (pinfunction "2_2") (pintype "passive"))
      (node (ref "IC1") (pin "6") (pinfunction "PH1-OSC_OUT_6") (pintype "output"))
      (node (ref "Q1") (pin "1") (pinfunction "1_1") (pintype "bidirectional"))
    )
    (net (code "94") (name "VDD") (class "Default")
      (node (ref "B2") (pin "2") (pinfunction "2_2") (pintype "passive"))
      (node (ref "C10") (pin "1") (pinfunction "1_1") (pintype "passive"))
      (node (ref "C11") (pin "1") (pinfunction "1_1") (pintype "passive"))
      (node (ref "C12") (pin "1") (pinfunction "1_1") (pintype "passive"))
      (node (ref "C13") (pin "1") (pinfunction "1_1") (pintype "passive"))
      (node (ref "C14") (pin "1") (pinfunction "1_1") (pintype "passive"))
      (node (ref "C20") (pin "1") (pinfunction "1_1") (pintype "passive"))
      (node (ref "IC1") (pin "1") (pinfunction "VBAT_1") (pintype "bidirectional"))
      (node (ref "IC1") (pin "19") (pinfunction "VDD1_19") (pintype "power_in"))
      (node (ref "IC1") (pin "32") (pinfunction "VDD2_32") (pintype "power_in"))
      (node (ref "IC1") (pin "48") (pinfunction "VDD3_48") (pintype "power_in"))
      (node (ref "IC1") (pin "64") (pinfunction "VDD4_64") (pintype "power_in"))
      (node (ref "R3") (pin "2") (pinfunction "2_2") (pintype "passive"))
    )
    (net (code "95") (name "VDDA") (class "Default")
      (node (ref "B3") (pin "2") (pinfunction "2_2") (pintype "passive"))
      (node (ref "C16") (pin "1") (pinfunction "1_1") (pintype "passive"))
      (node (ref "C17") (pin "1") (pinfunction "1_1") (pintype "passive"))
      (node (ref "IC1") (pin "13") (pinfunction "VDDA/VREF+_13") (pintype "power_in"))
    )
    (net (code "96") (name "unconnected-(IC1-BB9-Pad62)") (class "Default")
      (node (ref "IC1") (pin "62") (pinfunction "BB9_62") (pintype "bidirectional"))
    )
    (net (code "97") (name "unconnected-(IC1-PA0-Pad14)") (class "Default")
      (node (ref "IC1") (pin "14") (pinfunction "PA0_14") (pintype "bidirectional"))
    )
    (net (code "98") (name "unconnected-(IC1-PA1-Pad15)") (class "Default")
      (node (ref "IC1") (pin "15") (pinfunction "PA1_15") (pintype "bidirectional"))
    )
    (net (code "99") (name "unconnected-(IC1-PB4-Pad56)") (class "Default")
      (node (ref "IC1") (pin "56") (pinfunction "PB4_56") (pintype "bidirectional"))
    )
    (net (code "100") (name "unconnected-(IC1-PB5-Pad57)") (class "Default")
      (node (ref "IC1") (pin "57") (pinfunction "PB5_57") (pintype "bidirectional"))
    )
    (net (code "101") (name "unconnected-(IC1-PB8-Pad61)") (class "Default")
      (node (ref "IC1") (pin "61") (pinfunction "PB8_61") (pintype "bidirectional"))
    )
    (net (code "102") (name "unconnected-(IC1-PB12-Pad33)") (class "Default")
      (node (ref "IC1") (pin "33") (pinfunction "PB12_33") (pintype "bidirectional"))
    )
    (net (code "103") (name "unconnected-(IC1-PB13-Pad34)") (class "Default")
      (node (ref "IC1") (pin "34") (pinfunction "PB13_34") (pintype "bidirectional"))
    )
    (net (code "104") (name "unconnected-(IC1-PB14-Pad35)") (class "Default")
      (node (ref "IC1") (pin "35") (pinfunction "PB14_35") (pintype "bidirectional"))
    )
    (net (code "105") (name "unconnected-(IC1-PB15-Pad36)") (class "Default")
      (node (ref "IC1") (pin "36") (pinfunction "PB15_36") (pintype "bidirectional"))
    )
    (net (code "106") (name "unconnected-(IC1-PC0-Pad8)") (class "Default")
      (node (ref "IC1") (pin "8") (pinfunction "PC0_8") (pintype "bidirectional"))
    )
    (net (code "107") (name "unconnected-(IC1-PC1-Pad9)") (class "Default")
      (node (ref "IC1") (pin "9") (pinfunction "PC1_9") (pintype "bidirectional"))
    )
    (net (code "108") (name "unconnected-(IC1-PC2-Pad10)") (class "Default")
      (node (ref "IC1") (pin "10") (pinfunction "PC2_10") (pintype "bidirectional"))
    )
    (net (code "109") (name "unconnected-(IC1-PC3-Pad11)") (class "Default")
      (node (ref "IC1") (pin "11") (pinfunction "PC3_11") (pintype "bidirectional"))
    )
    (net (code "110") (name "unconnected-(IC1-PC4-Pad24)") (class "Default")
      (node (ref "IC1") (pin "24") (pinfunction "PC4_24") (pintype "bidirectional"))
    )
    (net (code "111") (name "unconnected-(IC1-PC6-Pad37)") (class "Default")
      (node (ref "IC1") (pin "37") (pinfunction "PC6_37") (pintype "bidirectional"))
    )
    (net (code "112") (name "unconnected-(IC1-PC13-Pad2)") (class "Default")
      (node (ref "IC1") (pin "2") (pinfunction "PC13_2") (pintype "bidirectional"))
    )
    (net (code "113") (name "unconnected-(J1-D+-Pad3)") (class "Default")
      (node (ref "J1") (pin "3") (pinfunction "D+_3") (pintype "bidirectional"))
    )
    (net (code "114") (name "unconnected-(J1-D--Pad2)") (class "Default")
      (node (ref "J1") (pin "2") (pinfunction "D-_2") (pintype "bidirectional"))
    )
    (net (code "115") (name "unconnected-(J1-GND_DRAIN-Pad7)") (class "Default")
      (node (ref "J1") (pin "7") (pinfunction "GND_DRAIN_7") (pintype "bidirectional"))
    )
    (net (code "116") (name "unconnected-(J1-STDA_SSRX+-Pad6)") (class "Default")
      (node (ref "J1") (pin "6") (pinfunction "STDA_SSRX+_6") (pintype "bidirectional"))
    )
    (net (code "117") (name "unconnected-(J1-STDA_SSRX--Pad5)") (class "Default")
      (node (ref "J1") (pin "5") (pinfunction "STDA_SSRX-_5") (pintype "bidirectional"))
    )
    (net (code "118") (name "unconnected-(J1-STDA_SSTX+-Pad9)") (class "Default")
      (node (ref "J1") (pin "9") (pinfunction "STDA_SSTX+_9") (pintype "bidirectional"))
    )
    (net (code "119") (name "unconnected-(J1-STDA_SSTX--Pad8)") (class "Default")
      (node (ref "J1") (pin "8") (pinfunction "STDA_SSTX-_8") (pintype "bidirectional"))
    )
    (net (code "120") (name "unconnected-(J2-D+-Pad3)") (class "Default")
      (node (ref "J2") (pin "3") (pinfunction "D+_3") (pintype "bidirectional"))
    )
    (net (code "121") (name "unconnected-(J2-D--Pad2)") (class "Default")
      (node (ref "J2") (pin "2") (pinfunction "D-_2") (pintype "bidirectional"))
    )
    (net (code "122") (name "unconnected-(J2-GND_DRAIN-Pad7)") (class "Default")
      (node (ref "J2") (pin "7") (pinfunction "GND_DRAIN_7") (pintype "bidirectional"))
    )
    (net (code "123") (name "unconnected-(J2-STDA_SSRX+-Pad6)") (class "Default")
      (node (ref "J2") (pin "6") (pinfunction "STDA_SSRX+_6") (pintype "bidirectional"))
    )
    (net (code "124") (name "unconnected-(J2-STDA_SSRX--Pad5)") (class "Default")
      (node (ref "J2") (pin "5") (pinfunction "STDA_SSRX-_5") (pintype "bidirectional"))
    )
    (net (code "125") (name "unconnected-(J2-STDA_SSTX+-Pad9)") (class "Default")
      (node (ref "J2") (pin "9") (pinfunction "STDA_SSTX+_9") (pintype "bidirectional"))
    )
    (net (code "126") (name "unconnected-(J2-STDA_SSTX--Pad8)") (class "Default")
      (node (ref "J2") (pin "8") (pinfunction "STDA_SSTX-_8") (pintype "bidirectional"))
    )
    (net (code "127") (name "unconnected-(SV1-Pad5)") (class "Default")
      (node (ref "SV1") (pin "5") (pinfunction "5_5") (pintype "passive"))
    )
    (net (code "128") (name "unconnected-(U$1-GPIO6-Pad18)") (class "Default")
      (node (ref "U$1") (pin "18") (pinfunction "GPIO6_18") (pintype "bidirectional"))
    )
    (net (code "129") (name "unconnected-(U$1-GPIO7-Pad17)") (class "Default")
      (node (ref "U$1") (pin "17") (pinfunction "GPIO7_17") (pintype "bidirectional"))
    )
    (net (code "130") (name "unconnected-(U$1-PCM_CLK-Pad24)") (class "Default")
      (node (ref "U$1") (pin "24") (pinfunction "PCM_CLK_24") (pintype "bidirectional"))
    )
    (net (code "131") (name "unconnected-(U$1-PCM_IN-Pad21)") (class "Default")
      (node (ref "U$1") (pin "21") (pinfunction "PCM_IN_21") (pintype "bidirectional"))
    )
    (net (code "132") (name "unconnected-(U$1-PCM_OUT-Pad22)") (class "Default")
      (node (ref "U$1") (pin "22") (pinfunction "PCM_OUT_22") (pintype "bidirectional"))
    )
    (net (code "133") (name "unconnected-(U$1-PCM_SYNC-Pad23)") (class "Default")
      (node (ref "U$1") (pin "23") (pinfunction "PCM_SYNC_23") (pintype "bidirectional"))
    )
    (net (code "134") (name "unconnected-(U$1-SPI_CLK-Pad27)") (class "Default")
      (node (ref "U$1") (pin "27") (pinfunction "SPI_CLK_27") (pintype "bidirectional"))
    )
    (net (code "135") (name "unconnected-(U$1-SPI_MISO-Pad26)") (class "Default")
      (node (ref "U$1") (pin "26") (pinfunction "SPI_MISO_26") (pintype "bidirectional"))
    )
    (net (code "136") (name "unconnected-(U$1-SPI_MOSI-Pad28)") (class "Default")
      (node (ref "U$1") (pin "28") (pinfunction "SPI_MOSI_28") (pintype "bidirectional"))
    )
    (net (code "137") (name "unconnected-(U$1-SPI_SS-Pad25)") (class "Default")
      (node (ref "U$1") (pin "25") (pinfunction "SPI_SS_25") (pintype "bidirectional"))
    )
    (net (code "138") (name "unconnected-(U$1-UART_CTS-Pad14)") (class "Default")
      (node (ref "U$1") (pin "14") (pinfunction "UART_CTS_14") (pintype "bidirectional"))
    )
    (net (code "139") (name "unconnected-(U$1-UART_RTS-Pad13)") (class "Default")
      (node (ref "U$1") (pin "13") (pinfunction "UART_RTS_13") (pintype "bidirectional"))
    )
    (net (code "140") (name "unconnected-(U$2-PadGPIO6)") (class "Default")
      (node (ref "U$2") (pin "GPIO6") (pinfunction "GPIO6_GPIO6") (pintype "bidirectional"))
    )
    (net (code "141") (name "unconnected-(U$2-PadGPIO7)") (class "Default")
      (node (ref "U$2") (pin "GPIO7") (pinfunction "GPIO7_GPIO7") (pintype "bidirectional"))
    )
    (net (code "142") (name "unconnected-(U$2-PadLED0)") (class "Default")
      (node (ref "U$2") (pin "LED0") (pinfunction "LED0_LED0") (pintype "bidirectional"))
    )
    (net (code "143") (name "unconnected-(U$2-PadLED1)") (class "Default")
      (node (ref "U$2") (pin "LED1") (pinfunction "LED1_LED1") (pintype "bidirectional"))
    )
    (net (code "144") (name "unconnected-(U$2-PadPCM_CLK)") (class "Default")
      (node (ref "U$2") (pin "PCM_CLK") (pinfunction "PCM_CLK_PCM_CLK") (pintype "bidirectional"))
    )
    (net (code "145") (name "unconnected-(U$2-PadPCM_IN)") (class "Default")
      (node (ref "U$2") (pin "PCM_IN") (pinfunction "PCM_IN_PCM_IN") (pintype "bidirectional"))
    )
    (net (code "146") (name "unconnected-(U$2-PadPCM_OUT)") (class "Default")
      (node (ref "U$2") (pin "PCM_OUT") (pinfunction "PCM_OUT_PCM_OUT") (pintype "bidirectional"))
    )
    (net (code "147") (name "unconnected-(U$2-PadPCM_SYNC)") (class "Default")
      (node (ref "U$2") (pin "PCM_SYNC") (pinfunction "PCM_SYNC_PCM_SYNC") (pintype "bidirectional"))
    )
    (net (code "148") (name "unconnected-(U$2-PadSPI_CLK)") (class "Default")
      (node (ref "U$2") (pin "SPI_CLK") (pinfunction "SPI_CLK_SPI_CLK") (pintype "bidirectional"))
    )
    (net (code "149") (name "unconnected-(U$2-PadSPI_MISO)") (class "Default")
      (node (ref "U$2") (pin "SPI_MISO") (pinfunction "SPI_MISO_SPI_MISO") (pintype "bidirectional"))
    )
    (net (code "150") (name "unconnected-(U$2-PadSPI_MOSI)") (class "Default")
      (node (ref "U$2") (pin "SPI_MOSI") (pinfunction "SPI_MOSI_SPI_MOSI") (pintype "bidirectional"))
    )
    (net (code "151") (name "unconnected-(U$2-PadSPI_SS)") (class "Default")
      (node (ref "U$2") (pin "SPI_SS") (pinfunction "SPI_SS_SPI_SS") (pintype "bidirectional"))
    )
    (net (code "152") (name "unconnected-(U$2-PadUART_CTS)") (class "Default")
      (node (ref "U$2") (pin "UART_CTS") (pinfunction "UART_CTS_UART_CTS") (pintype "bidirectional"))
    )
    (net (code "153") (name "unconnected-(U$2-PadUART_RTS)") (class "Default")
      (node (ref "U$2") (pin "UART_RTS") (pinfunction "UART_RTS_UART_RTS") (pintype "bidirectional"))
    )
    (net (code "154") (name "unconnected-(USB1-PadD+)") (class "Default")
      (node (ref "USB1") (pin "D+") (pinfunction "D+_D+") (pintype "bidirectional"))
    )
    (net (code "155") (name "unconnected-(USB1-PadD-)") (class "Default")
      (node (ref "USB1") (pin "D-") (pinfunction "D-_D-") (pintype "bidirectional"))
    )
    (net (code "156") (name "unconnected-(USB1-PadID)") (class "Default")
      (node (ref "USB1") (pin "ID") (pinfunction "ID_ID") (pintype "bidirectional"))
    )
    (net (code "157") (name "unconnected-(USB2-PadID)") (class "Default")
      (node (ref "USB2") (pin "ID") (pinfunction "ID_ID") (pintype "bidirectional"))
    )
    (net (code "158") (name "~{RESET}") (class "Default")
      (node (ref "C21") (pin "1") (pinfunction "1_1") (pintype "passive"))
      (node (ref "IC1") (pin "7") (pinfunction "NRST_7") (pintype "input"))
      (node (ref "R3") (pin "1") (pinfunction "1_1") (pintype "passive"))
      (node (ref "RESET") (pin "3") (pinfunction "3_3") (pintype "passive"))
      (node (ref "RESET") (pin "4") (pinfunction "4_4") (pintype "passive"))
    )
  )
)
